# VESC_KS75600_ana_con.net
KiCad netlist of a schematic drawn in Altium Designer
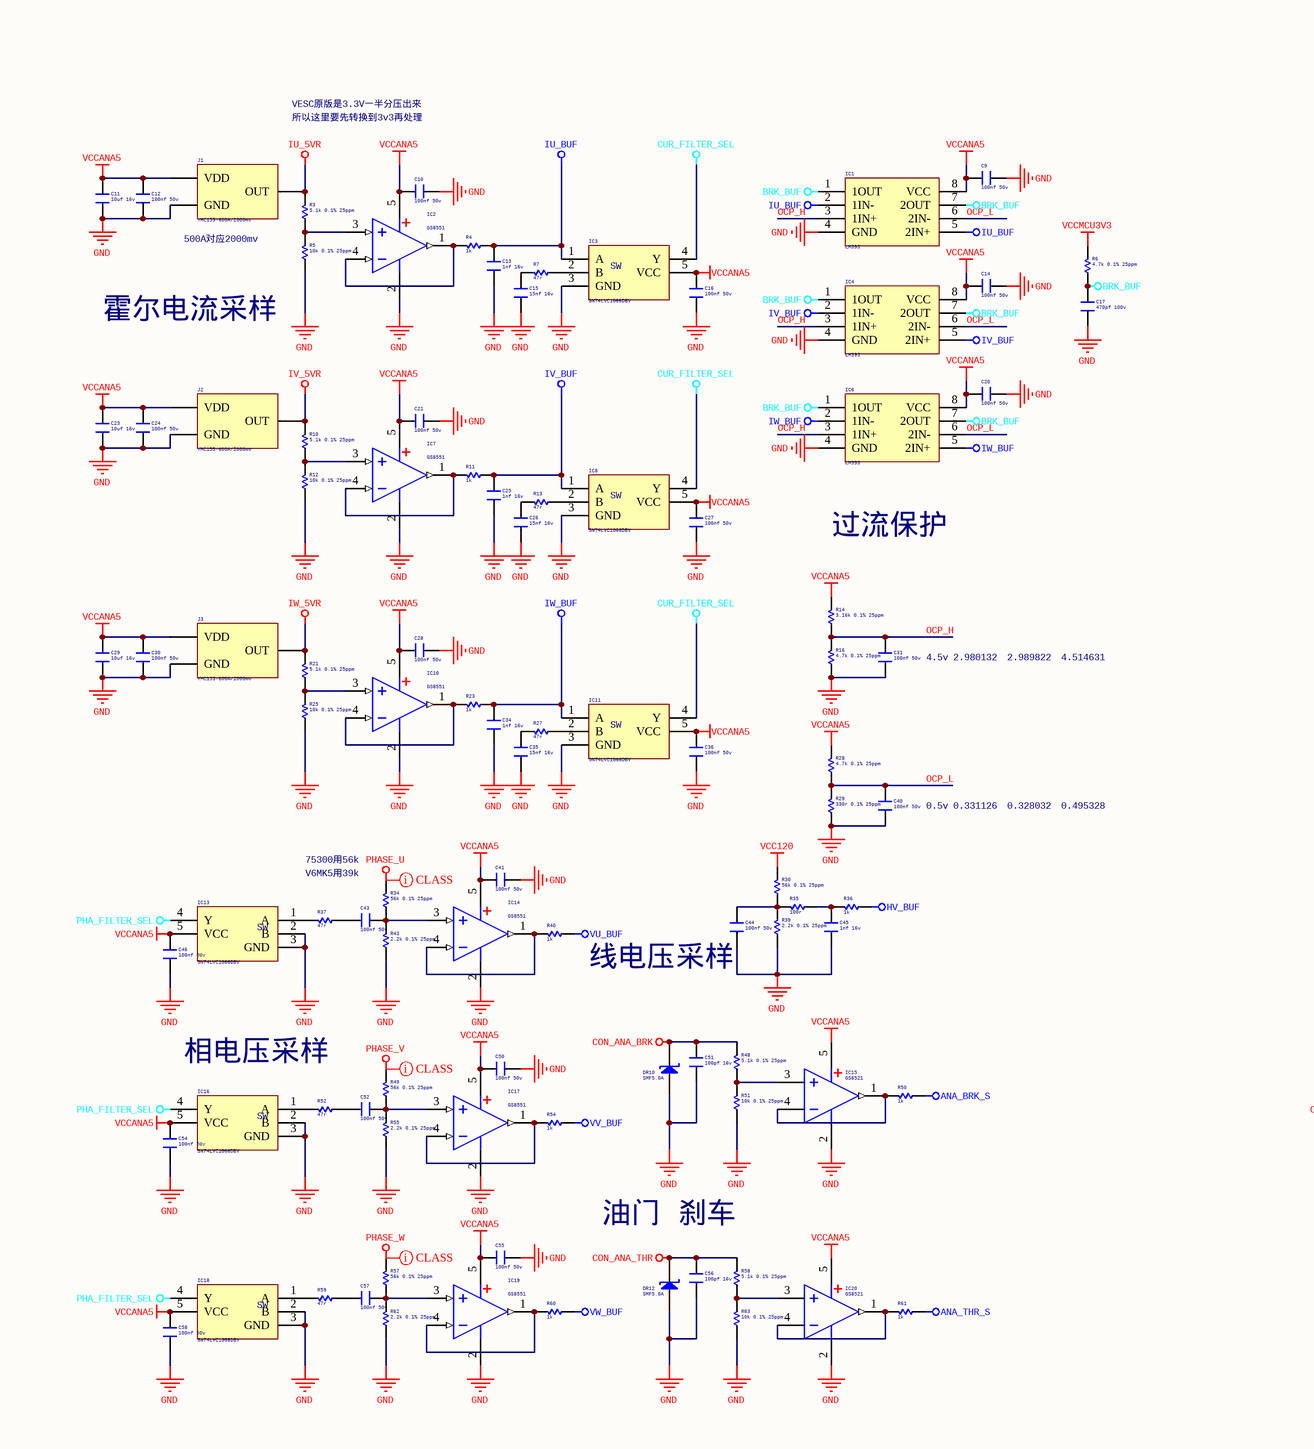
[diagram p0: VESC_KS75600_ana_con.SchDoc, left]
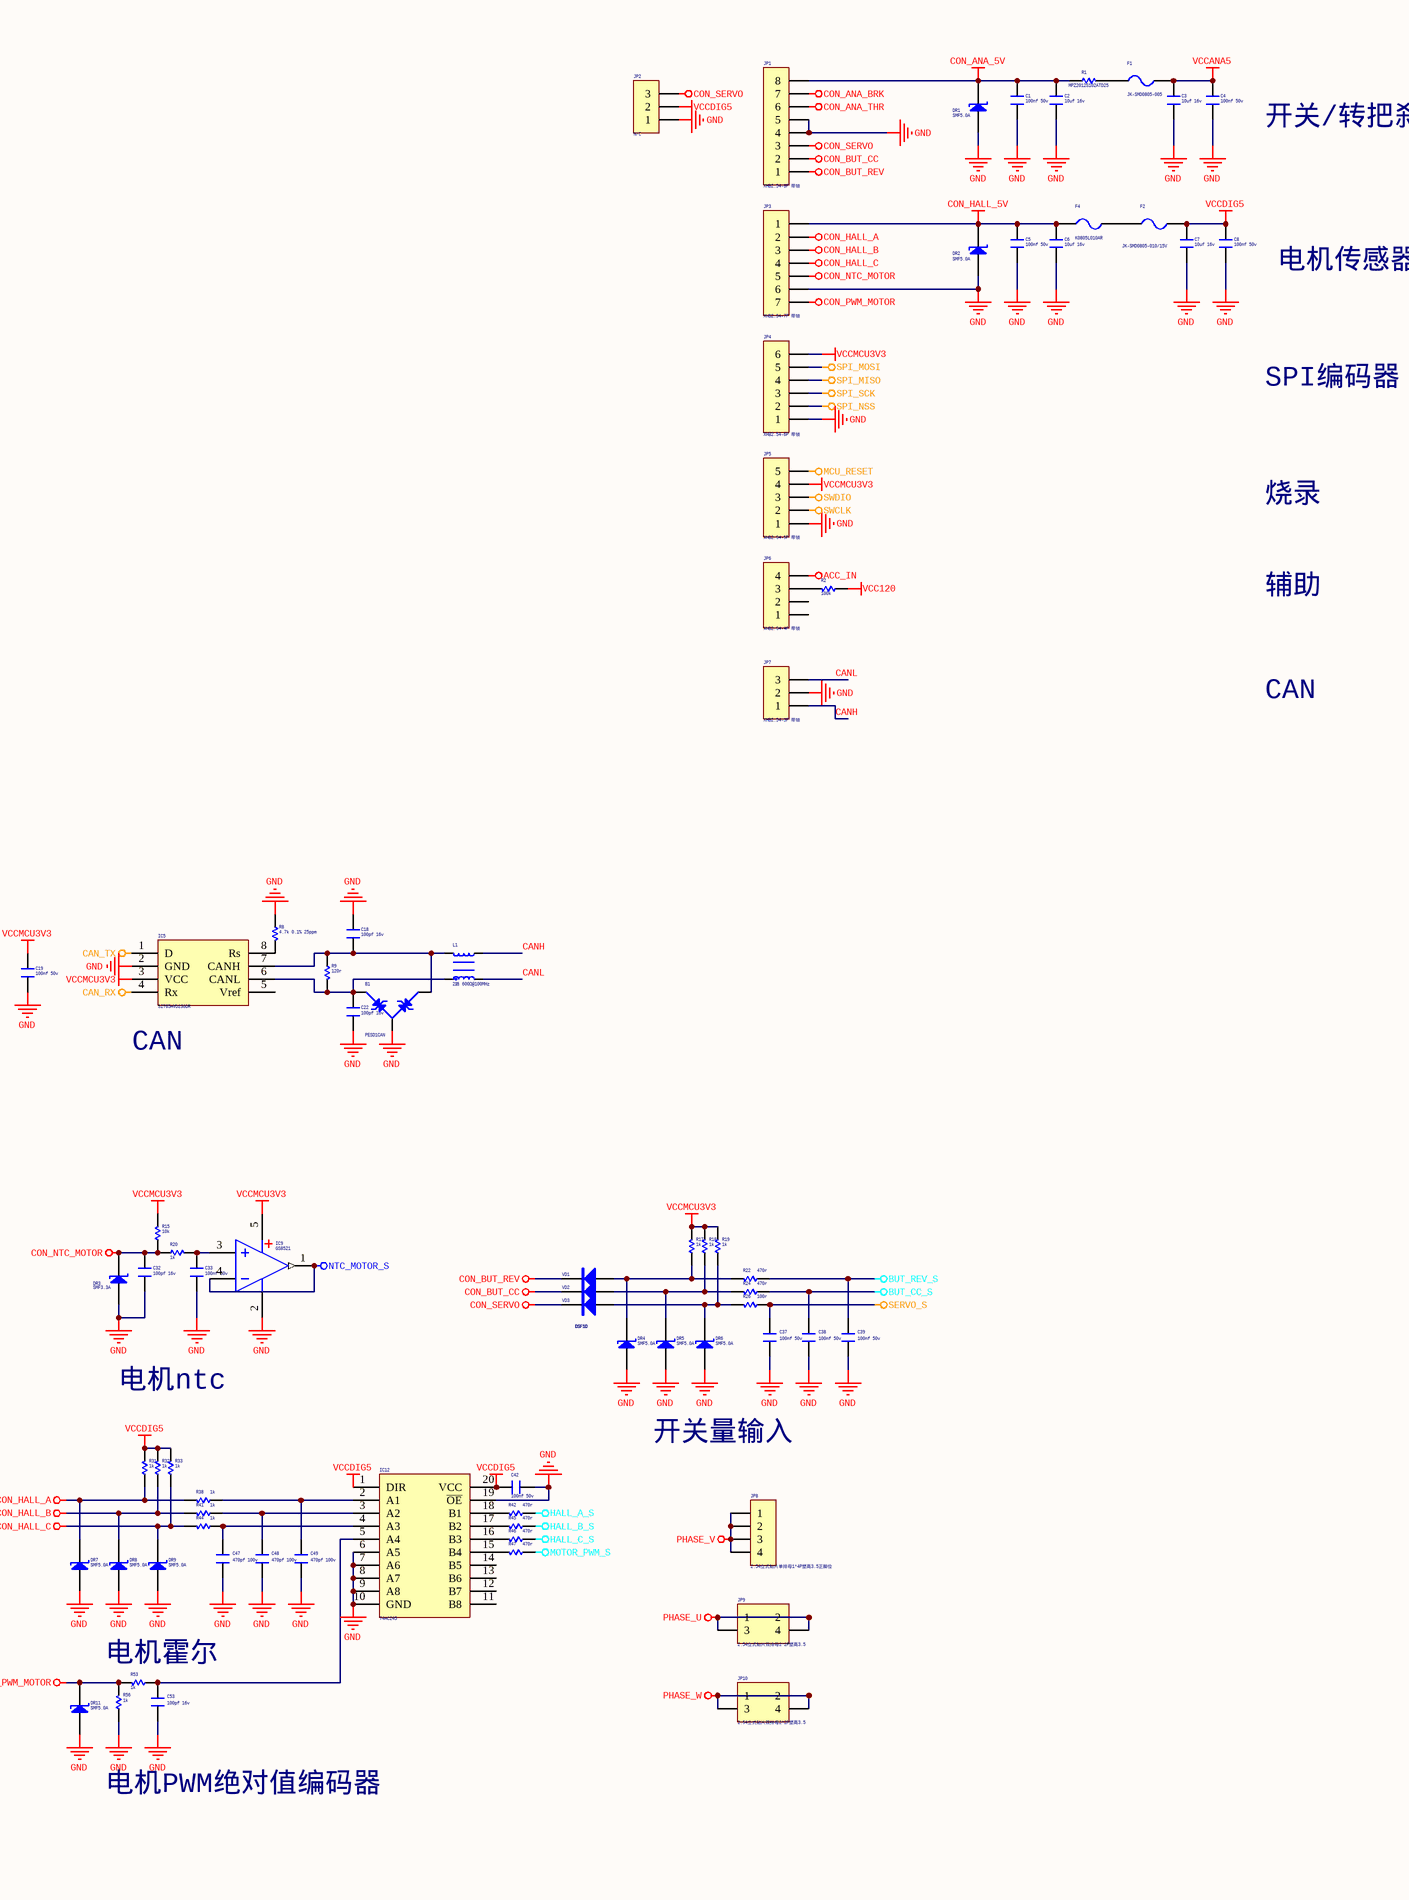
[diagram p1: VESC_KS75600_ana_con.SchDoc, right]

(export (version "E")
  (design (tool "Eeschema 10.0.6"))
  (components
    (comp (ref "B1")
      (value "PESD1CAN")
      (footprint "SOT23-3L")
      (description "7V+12V 双向双路TVS")
      (libsource (lib "二极管-整流桥") (part "SM712"))
    )
    (comp (ref "C1")
      (value "100nf 50v")
      (footprint "C 0603")
      (description "无极性贴片电容")
      (fields (field (name "VOLTAGE") "50v"))
      (libsource (lib "电阻-电容-电感") (part "C"))
    )
    (comp (ref "C2")
      (value "10uf 16v")
      (footprint "C 0805")
      (description "无极性贴片电容")
      (fields (field (name "VOLTAGE") "16v"))
      (libsource (lib "电阻-电容-电感") (part "C"))
    )
    (comp (ref "C3")
      (value "10uf 16v")
      (footprint "C 0805")
      (description "无极性贴片电容")
      (fields (field (name "VOLTAGE") "16v"))
      (libsource (lib "电阻-电容-电感") (part "C"))
    )
    (comp (ref "C4")
      (value "100nf 50v")
      (footprint "C 0603")
      (description "无极性贴片电容")
      (fields (field (name "VOLTAGE") "50v"))
      (libsource (lib "电阻-电容-电感") (part "C"))
    )
    (comp (ref "C5")
      (value "100nf 50v")
      (footprint "C 0603")
      (description "无极性贴片电容")
      (fields (field (name "VOLTAGE") "50v"))
      (libsource (lib "电阻-电容-电感") (part "C"))
    )
    (comp (ref "C6")
      (value "10uf 16v")
      (footprint "C 0805")
      (description "无极性贴片电容")
      (fields (field (name "VOLTAGE") "16v"))
      (libsource (lib "电阻-电容-电感") (part "C"))
    )
    (comp (ref "C7")
      (value "10uf 16v")
      (footprint "C 0805")
      (description "无极性贴片电容")
      (fields (field (name "VOLTAGE") "16v"))
      (libsource (lib "电阻-电容-电感") (part "C"))
    )
    (comp (ref "C8")
      (value "100nf 50v")
      (footprint "C 0603")
      (description "无极性贴片电容")
      (fields (field (name "VOLTAGE") "50v"))
      (libsource (lib "电阻-电容-电感") (part "C"))
    )
    (comp (ref "C9")
      (value "100nf 50v")
      (footprint "C 0603")
      (description "无极性贴片电容")
      (fields (field (name "VOLTAGE") "50v"))
      (libsource (lib "电阻-电容-电感") (part "C"))
    )
    (comp (ref "C10")
      (value "100nf 50v")
      (footprint "C 0603")
      (description "无极性贴片电容")
      (fields (field (name "VOLTAGE") "50v"))
      (libsource (lib "电阻-电容-电感") (part "C"))
    )
    (comp (ref "C11")
      (value "10uf 16v")
      (footprint "C 0805")
      (description "无极性贴片电容")
      (fields (field (name "VOLTAGE") "16v"))
      (libsource (lib "电阻-电容-电感") (part "C"))
    )
    (comp (ref "C12")
      (value "100nf 50v")
      (footprint "C 0603")
      (description "无极性贴片电容")
      (fields (field (name "VOLTAGE") "50v"))
      (libsource (lib "电阻-电容-电感") (part "C"))
    )
    (comp (ref "C13")
      (value "1nf 16v")
      (footprint "C 0603")
      (description "无极性贴片电容")
      (fields (field (name "VOLTAGE") "16v"))
      (libsource (lib "电阻-电容-电感") (part "C"))
    )
    (comp (ref "C14")
      (value "100nf 50v")
      (footprint "C 0603")
      (description "无极性贴片电容")
      (fields (field (name "VOLTAGE") "50v"))
      (libsource (lib "电阻-电容-电感") (part "C"))
    )
    (comp (ref "C15")
      (value "15nf 16v")
      (footprint "C 0603")
      (description "无极性贴片电容")
      (fields (field (name "VOLTAGE") "16v"))
      (libsource (lib "电阻-电容-电感") (part "C"))
    )
    (comp (ref "C16")
      (value "100nf 50v")
      (footprint "C 0603")
      (description "无极性贴片电容")
      (fields (field (name "VOLTAGE") "50v"))
      (libsource (lib "电阻-电容-电感") (part "C"))
    )
    (comp (ref "C17")
      (value "470pf 100v")
      (footprint "C 0805")
      (description "无极性贴片电容")
      (fields (field (name "VOLTAGE") "100v"))
      (libsource (lib "电阻-电容-电感") (part "C"))
    )
    (comp (ref "C18")
      (value "100pf 16v")
      (footprint "C 0603")
      (description "无极性贴片电容")
      (fields (field (name "VOLTAGE") "16v"))
      (libsource (lib "电阻-电容-电感") (part "C"))
    )
    (comp (ref "C19")
      (value "100nf 50v")
      (footprint "C 0603")
      (description "无极性贴片电容")
      (fields (field (name "VOLTAGE") "50v"))
      (libsource (lib "电阻-电容-电感") (part "C"))
    )
    (comp (ref "C20")
      (value "100nf 50v")
      (footprint "C 0603")
      (description "无极性贴片电容")
      (fields (field (name "VOLTAGE") "50v"))
      (libsource (lib "电阻-电容-电感") (part "C"))
    )
    (comp (ref "C21")
      (value "100nf 50v")
      (footprint "C 0603")
      (description "无极性贴片电容")
      (fields (field (name "VOLTAGE") "50v"))
      (libsource (lib "电阻-电容-电感") (part "C"))
    )
    (comp (ref "C22")
      (value "100pf 16v")
      (footprint "C 0603")
      (description "无极性贴片电容")
      (fields (field (name "VOLTAGE") "16v"))
      (libsource (lib "电阻-电容-电感") (part "C"))
    )
    (comp (ref "C23")
      (value "10uf 16v")
      (footprint "C 0805")
      (description "无极性贴片电容")
      (fields (field (name "VOLTAGE") "16v"))
      (libsource (lib "电阻-电容-电感") (part "C"))
    )
    (comp (ref "C24")
      (value "100nf 50v")
      (footprint "C 0603")
      (description "无极性贴片电容")
      (fields (field (name "VOLTAGE") "50v"))
      (libsource (lib "电阻-电容-电感") (part "C"))
    )
    (comp (ref "C25")
      (value "1nf 16v")
      (footprint "C 0603")
      (description "无极性贴片电容")
      (fields (field (name "VOLTAGE") "16v"))
      (libsource (lib "电阻-电容-电感") (part "C"))
    )
    (comp (ref "C26")
      (value "15nf 16v")
      (footprint "C 0603")
      (description "无极性贴片电容")
      (fields (field (name "VOLTAGE") "16v"))
      (libsource (lib "电阻-电容-电感") (part "C"))
    )
    (comp (ref "C27")
      (value "100nf 50v")
      (footprint "C 0603")
      (description "无极性贴片电容")
      (fields (field (name "VOLTAGE") "50v"))
      (libsource (lib "电阻-电容-电感") (part "C"))
    )
    (comp (ref "C28")
      (value "100nf 50v")
      (footprint "C 0603")
      (description "无极性贴片电容")
      (fields (field (name "VOLTAGE") "50v"))
      (libsource (lib "电阻-电容-电感") (part "C"))
    )
    (comp (ref "C29")
      (value "10uf 16v")
      (footprint "C 0805")
      (description "无极性贴片电容")
      (fields (field (name "VOLTAGE") "16v"))
      (libsource (lib "电阻-电容-电感") (part "C"))
    )
    (comp (ref "C30")
      (value "100nf 50v")
      (footprint "C 0603")
      (description "无极性贴片电容")
      (fields (field (name "VOLTAGE") "50v"))
      (libsource (lib "电阻-电容-电感") (part "C"))
    )
    (comp (ref "C31")
      (value "100nf 50v")
      (footprint "C 0603")
      (description "无极性贴片电容")
      (fields (field (name "VOLTAGE") "50v"))
      (libsource (lib "电阻-电容-电感") (part "C"))
    )
    (comp (ref "C32")
      (value "100pf 16v")
      (footprint "C 0603")
      (description "无极性贴片电容")
      (fields (field (name "VOLTAGE") "16v"))
      (libsource (lib "电阻-电容-电感") (part "C"))
    )
    (comp (ref "C33")
      (value "100nf 50v")
      (footprint "C 0603")
      (description "无极性贴片电容")
      (fields (field (name "VOLTAGE") "50v"))
      (libsource (lib "电阻-电容-电感") (part "C"))
    )
    (comp (ref "C34")
      (value "1nf 16v")
      (footprint "C 0603")
      (description "无极性贴片电容")
      (fields (field (name "VOLTAGE") "16v"))
      (libsource (lib "电阻-电容-电感") (part "C"))
    )
    (comp (ref "C35")
      (value "15nf 16v")
      (footprint "C 0603")
      (description "无极性贴片电容")
      (fields (field (name "VOLTAGE") "16v"))
      (libsource (lib "电阻-电容-电感") (part "C"))
    )
    (comp (ref "C36")
      (value "100nf 50v")
      (footprint "C 0603")
      (description "无极性贴片电容")
      (fields (field (name "VOLTAGE") "50v"))
      (libsource (lib "电阻-电容-电感") (part "C"))
    )
    (comp (ref "C37")
      (value "100nf 50v")
      (footprint "C 0805")
      (description "无极性贴片电容")
      (fields (field (name "VOLTAGE") "50v"))
      (libsource (lib "电阻-电容-电感") (part "C"))
    )
    (comp (ref "C38")
      (value "100nf 50v")
      (footprint "C 0805")
      (description "无极性贴片电容")
      (fields (field (name "VOLTAGE") "50v"))
      (libsource (lib "电阻-电容-电感") (part "C"))
    )
    (comp (ref "C39")
      (value "100nf 50v")
      (footprint "C 0805")
      (description "无极性贴片电容")
      (fields (field (name "VOLTAGE") "50v"))
      (libsource (lib "电阻-电容-电感") (part "C"))
    )
    (comp (ref "C40")
      (value "100nf 50v")
      (footprint "C 0603")
      (description "无极性贴片电容")
      (fields (field (name "VOLTAGE") "50v"))
      (libsource (lib "电阻-电容-电感") (part "C"))
    )
    (comp (ref "C41")
      (value "100nf 50v")
      (footprint "C 0603")
      (description "无极性贴片电容")
      (fields (field (name "VOLTAGE") "50v"))
      (libsource (lib "电阻-电容-电感") (part "C"))
    )
    (comp (ref "C42")
      (value "100nf 50v")
      (footprint "C 0603")
      (description "无极性贴片电容")
      (fields (field (name "VOLTAGE") "50v"))
      (libsource (lib "电阻-电容-电感") (part "C"))
    )
    (comp (ref "C43")
      (value "100nf 50v")
      (footprint "C 0805")
      (description "无极性贴片电容")
      (fields (field (name "VOLTAGE") "50v"))
      (libsource (lib "电阻-电容-电感") (part "C"))
    )
    (comp (ref "C44")
      (value "100nf 50v")
      (footprint "C 0805")
      (description "无极性贴片电容")
      (fields (field (name "VOLTAGE") "50v"))
      (libsource (lib "电阻-电容-电感") (part "C"))
    )
    (comp (ref "C45")
      (value "1nf 16v")
      (footprint "C 0603")
      (description "无极性贴片电容")
      (fields (field (name "VOLTAGE") "16v"))
      (libsource (lib "电阻-电容-电感") (part "C"))
    )
    (comp (ref "C46")
      (value "100nf 50v")
      (footprint "C 0603")
      (description "无极性贴片电容")
      (fields (field (name "VOLTAGE") "50v"))
      (libsource (lib "电阻-电容-电感") (part "C"))
    )
    (comp (ref "C47")
      (value "470pf 100v")
      (footprint "C 0805")
      (description "无极性贴片电容")
      (fields (field (name "VOLTAGE") "100v"))
      (libsource (lib "电阻-电容-电感") (part "C"))
    )
    (comp (ref "C48")
      (value "470pf 100v")
      (footprint "C 0805")
      (description "无极性贴片电容")
      (fields (field (name "VOLTAGE") "100v"))
      (libsource (lib "电阻-电容-电感") (part "C"))
    )
    (comp (ref "C49")
      (value "470pf 100v")
      (footprint "C 0805")
      (description "无极性贴片电容")
      (fields (field (name "VOLTAGE") "100v"))
      (libsource (lib "电阻-电容-电感") (part "C"))
    )
    (comp (ref "C50")
      (value "100nf 50v")
      (footprint "C 0603")
      (description "无极性贴片电容")
      (fields (field (name "VOLTAGE") "50v"))
      (libsource (lib "电阻-电容-电感") (part "C"))
    )
    (comp (ref "C51")
      (value "100pf 16v")
      (footprint "C 0603")
      (description "无极性贴片电容")
      (fields (field (name "VOLTAGE") "16v"))
      (libsource (lib "电阻-电容-电感") (part "C"))
    )
    (comp (ref "C52")
      (value "100nf 50v")
      (footprint "C 0805")
      (description "无极性贴片电容")
      (fields (field (name "VOLTAGE") "50v"))
      (libsource (lib "电阻-电容-电感") (part "C"))
    )
    (comp (ref "C53")
      (value "100pf 16v")
      (footprint "C 0805")
      (description "无极性贴片电容")
      (fields (field (name "VOLTAGE") "16v"))
      (libsource (lib "电阻-电容-电感") (part "C"))
    )
    (comp (ref "C54")
      (value "100nf 50v")
      (footprint "C 0603")
      (description "无极性贴片电容")
      (fields (field (name "VOLTAGE") "50v"))
      (libsource (lib "电阻-电容-电感") (part "C"))
    )
    (comp (ref "C55")
      (value "100nf 50v")
      (footprint "C 0603")
      (description "无极性贴片电容")
      (fields (field (name "VOLTAGE") "50v"))
      (libsource (lib "电阻-电容-电感") (part "C"))
    )
    (comp (ref "C56")
      (value "100pf 16v")
      (footprint "C 0603")
      (description "无极性贴片电容")
      (fields (field (name "VOLTAGE") "16v"))
      (libsource (lib "电阻-电容-电感") (part "C"))
    )
    (comp (ref "C57")
      (value "100nf 50v")
      (footprint "C 0805")
      (description "无极性贴片电容")
      (fields (field (name "VOLTAGE") "50v"))
      (libsource (lib "电阻-电容-电感") (part "C"))
    )
    (comp (ref "C58")
      (value "100nf 50v")
      (footprint "C 0603")
      (description "无极性贴片电容")
      (fields (field (name "VOLTAGE") "50v"))
      (libsource (lib "电阻-电容-电感") (part "C"))
    )
    (comp (ref "DR1")
      (value "SMF5.0A")
      (footprint "SOD-123F")
      (description "瞬态电压抑制二极管(单向)")
      (libsource (lib "二极管-整流桥") (part "DR_S"))
    )
    (comp (ref "DR2")
      (value "SMF5.0A")
      (footprint "SOD-123F")
      (description "瞬态电压抑制二极管(单向)")
      (libsource (lib "二极管-整流桥") (part "DR_S"))
    )
    (comp (ref "DR3")
      (value "SMF3.3A")
      (footprint "SOD-123F")
      (description "瞬态电压抑制二极管(单向)")
      (libsource (lib "二极管-整流桥") (part "DR_S"))
    )
    (comp (ref "DR4")
      (value "SMF5.0A")
      (footprint "SOD-123F")
      (description "瞬态电压抑制二极管(单向)")
      (libsource (lib "二极管-整流桥") (part "DR_S"))
    )
    (comp (ref "DR5")
      (value "SMF5.0A")
      (footprint "SOD-123F")
      (description "瞬态电压抑制二极管(单向)")
      (libsource (lib "二极管-整流桥") (part "DR_S"))
    )
    (comp (ref "DR6")
      (value "SMF5.0A")
      (footprint "SOD-123F")
      (description "瞬态电压抑制二极管(单向)")
      (libsource (lib "二极管-整流桥") (part "DR_S"))
    )
    (comp (ref "DR7")
      (value "SMF5.0A")
      (footprint "SOD-123F")
      (description "瞬态电压抑制二极管(单向)")
      (libsource (lib "二极管-整流桥") (part "DR_S"))
    )
    (comp (ref "DR8")
      (value "SMF5.0A")
      (footprint "SOD-123F")
      (description "瞬态电压抑制二极管(单向)")
      (libsource (lib "二极管-整流桥") (part "DR_S"))
    )
    (comp (ref "DR9")
      (value "SMF5.0A")
      (footprint "SOD-123F")
      (description "瞬态电压抑制二极管(单向)")
      (libsource (lib "二极管-整流桥") (part "DR_S"))
    )
    (comp (ref "DR10")
      (value "SMF5.0A")
      (footprint "SOD-123F")
      (description "瞬态电压抑制二极管(单向)")
      (libsource (lib "二极管-整流桥") (part "DR_S"))
    )
    (comp (ref "DR11")
      (value "SMF5.0A")
      (footprint "SOD-123F")
      (description "瞬态电压抑制二极管(单向)")
      (libsource (lib "二极管-整流桥") (part "DR_S"))
    )
    (comp (ref "DR12")
      (value "SMF5.0A")
      (footprint "SOD-123F")
      (description "瞬态电压抑制二极管(单向)")
      (libsource (lib "二极管-整流桥") (part "DR_S"))
    )
    (comp (ref "F1")
      (value "JK-SMD0805-005")
      (footprint "FU 0805")
      (description "贴片保险丝")
      (libsource (lib "保险丝-晶振") (part "FU"))
    )
    (comp (ref "F2")
      (value "JK-SMD0805-010/15V")
      (footprint "FU 0805")
      (description "贴片保险丝")
      (libsource (lib "保险丝-晶振") (part "FU"))
    )
    (comp (ref "F4")
      (value "K0805L010AR")
      (footprint "FU 0805")
      (description "贴片保险丝")
      (libsource (lib "保险丝-晶振") (part "FU"))
    )
    (comp (ref "IC1")
      (value "LM393")
      (footprint "SOP8_N")
      (description "双路电压比较")
      (libsource (lib "IC芯片") (part "LM393_A"))
    )
    (comp (ref "IC2")
      (value "GS8551")
      (footprint "SOT23-5L")
      (description "单运放 SOT23-5")
      (libsource (lib "IC芯片") (part "GS8331"))
    )
    (comp (ref "IC3")
      (value "SN74LVC1G66DBV")
      (footprint "SOT23-5N")
      (description "单路常开模拟开关 0.5ns 5.5Ω")
      (libsource (lib "") (part "SN74LVC1G66_1"))
    )
    (comp (ref "IC4")
      (value "LM393")
      (footprint "SOP8_N")
      (description "双路电压比较")
      (libsource (lib "IC芯片") (part "LM393_A"))
    )
    (comp (ref "IC5")
      (value "SIT65HVD230DR")
      (footprint "SOP8_N")
      (description "CAN芯片")
      (libsource (lib "IC芯片") (part "SN65HVD230"))
    )
    (comp (ref "IC6")
      (value "LM393")
      (footprint "SOP8_N")
      (description "双路电压比较")
      (libsource (lib "IC芯片") (part "LM393_A"))
    )
    (comp (ref "IC7")
      (value "GS8551")
      (footprint "SOT23-5L")
      (description "单运放 SOT23-5")
      (libsource (lib "IC芯片") (part "GS8331"))
    )
    (comp (ref "IC8")
      (value "SN74LVC1G66DBV")
      (footprint "SOT23-5N")
      (description "单路常开模拟开关 0.5ns 5.5Ω")
      (libsource (lib "") (part "SN74LVC1G66_1"))
    )
    (comp (ref "IC9")
      (value "GS8521")
      (footprint "SOT23-5N")
      (description "单运放 SOT23-5")
      (libsource (lib "") (part "GS8331_1"))
    )
    (comp (ref "IC10")
      (value "GS8551")
      (footprint "SOT23-5L")
      (description "单运放 SOT23-5")
      (libsource (lib "IC芯片") (part "GS8331"))
    )
    (comp (ref "IC11")
      (value "SN74LVC1G66DBV")
      (footprint "SOT23-5N")
      (description "单路常开模拟开关 0.5ns 5.5Ω")
      (libsource (lib "") (part "SN74LVC1G66_1"))
    )
    (comp (ref "IC12")
      (value "74HC245")
      (footprint "TSSOP20_N")
      (description "八线收发器")
      (libsource (lib "74系列芯片") (part "74HC245"))
    )
    (comp (ref "IC13")
      (value "SN74LVC1G66DBV")
      (footprint "SOT23-5N")
      (description "单路常开模拟开关 0.5ns 5.5Ω")
      (libsource (lib "74系列芯片") (part "SN74LVC1G66"))
    )
    (comp (ref "IC14")
      (value "GS8551")
      (footprint "SOT23-5L")
      (description "单运放 SOT23-5")
      (libsource (lib "IC芯片") (part "GS8331"))
    )
    (comp (ref "IC15")
      (value "GS8521")
      (footprint "SOT23-5N")
      (description "单运放 SOT23-5")
      (libsource (lib "") (part "GS8331_1"))
    )
    (comp (ref "IC16")
      (value "SN74LVC1G66DBV")
      (footprint "SOT23-5N")
      (description "单路常开模拟开关 0.5ns 5.5Ω")
      (libsource (lib "74系列芯片") (part "SN74LVC1G66"))
    )
    (comp (ref "IC17")
      (value "GS8551")
      (footprint "SOT23-5L")
      (description "单运放 SOT23-5")
      (libsource (lib "IC芯片") (part "GS8331"))
    )
    (comp (ref "IC18")
      (value "SN74LVC1G66DBV")
      (footprint "SOT23-5N")
      (description "单路常开模拟开关 0.5ns 5.5Ω")
      (libsource (lib "74系列芯片") (part "SN74LVC1G66"))
    )
    (comp (ref "IC19")
      (value "GS8551")
      (footprint "SOT23-5L")
      (description "单运放 SOT23-5")
      (libsource (lib "IC芯片") (part "GS8331"))
    )
    (comp (ref "IC20")
      (value "GS8521")
      (footprint "SOT23-5N")
      (description "单运放 SOT23-5")
      (libsource (lib "") (part "GS8331_1"))
    )
    (comp (ref "J1")
      (value "YMC15S-600A/2000mv")
      (footprint "YMC15S")
      (description "源弥科技 开环霍尔传感器")
      (libsource (lib "传感元件") (part "YMC15S"))
    )
    (comp (ref "J2")
      (value "YMC15S-600A/2000mv")
      (footprint "YMC15S")
      (description "源弥科技 开环霍尔传感器")
      (libsource (lib "传感元件") (part "YMC15S"))
    )
    (comp (ref "J3")
      (value "YMC15S-600A/2000mv")
      (footprint "YMC15S")
      (description "源弥科技 开环霍尔传感器")
      (libsource (lib "传感元件") (part "YMC15S"))
    )
    (comp (ref "JP1")
      (value "XHB2.54-8P 带锁")
      (footprint "XH2.54-8P")
      (description "8P接插件")
      (libsource (lib "接插件") (part "Header 8"))
    )
    (comp (ref "JP2")
      (value "N/C")
      (footprint "HDR-1X3")
      (description "3P接插件")
      (libsource (lib "接插件") (part "Header 3"))
    )
    (comp (ref "JP3")
      (value "XHB2.54-7P 带锁")
      (footprint "XH2.54-7P")
      (description "7P接插件")
      (libsource (lib "接插件") (part "Header 7"))
    )
    (comp (ref "JP4")
      (value "XHB2.54-6P 带锁")
      (footprint "XH2.54-6P")
      (description "6P接插件")
      (libsource (lib "接插件") (part "Header 6"))
    )
    (comp (ref "JP5")
      (value "XHB2.54-5P 带锁")
      (footprint "XH2.54-5P")
      (description "5P接插件")
      (libsource (lib "接插件") (part "Header 5"))
    )
    (comp (ref "JP6")
      (value "XHB2.54-4P 带锁")
      (footprint "XH2.54-4P")
      (description "4P接插件")
      (libsource (lib "接插件") (part "Header 4"))
    )
    (comp (ref "JP7")
      (value "XHB2.54-3P 带锁")
      (footprint "XH2.54-3P")
      (description "3P接插件")
      (libsource (lib "接插件") (part "Header 3"))
    )
    (comp (ref "JP8")
      (value "2.54立式贴片单排母1*4P塑高3.5正脚位")
      (footprint "2.54立贴错位排母 4P")
      (description "4P接插件")
      (libsource (lib "") (part "Header 4_1"))
    )
    (comp (ref "JP9")
      (value "2.54立式贴片双排母2*2P塑高3.5")
      (footprint "贴片2.54双排母 pcb开孔")
      (description "2*2P接插件")
      (libsource (lib "接插件") (part "Header 2X2"))
    )
    (comp (ref "JP10")
      (value "2.54立式贴片双排母2*2P塑高3.5")
      (footprint "贴片2.54双排母 pcb开孔")
      (description "2*2P接插件")
      (libsource (lib "接插件") (part "Header 2X2"))
    )
    (comp (ref "L1")
      (value "2路 600Ω@100MHz")
      (footprint "D_C_C_1206")
      (description "共模电感")
      (libsource (lib "电阻-电容-电感") (part "L-CMC"))
    )
    (comp (ref "R1")
      (value "MPZ2012S102ATD25")
      (footprint "R 0805")
      (description "贴片电阻")
      (libsource (lib "电阻-电容-电感") (part "R"))
    )
    (comp (ref "R2")
      (value "100k")
      (footprint "R 0805")
      (description "贴片电阻")
      (libsource (lib "电阻-电容-电感") (part "R"))
    )
    (comp (ref "R3")
      (value "5.1k 0.1% 25ppm")
      (footprint "R 0805-HP")
      (description "贴片电阻")
      (libsource (lib "电阻-电容-电感") (part "R"))
    )
    (comp (ref "R4")
      (value "1k")
      (footprint "R 0603")
      (description "贴片电阻")
      (libsource (lib "电阻-电容-电感") (part "R"))
    )
    (comp (ref "R5")
      (value "10k 0.1% 25ppm")
      (footprint "R 0805-HP")
      (description "贴片电阻")
      (libsource (lib "电阻-电容-电感") (part "R"))
    )
    (comp (ref "R6")
      (value "4.7k 0.1% 25ppm")
      (footprint "R 0805")
      (description "贴片电阻")
      (libsource (lib "电阻-电容-电感") (part "R"))
    )
    (comp (ref "R7")
      (value "47r")
      (footprint "R 0603")
      (description "贴片电阻")
      (libsource (lib "电阻-电容-电感") (part "R"))
    )
    (comp (ref "R8")
      (value "4.7k 0.1% 25ppm")
      (footprint "R 0805")
      (description "贴片电阻")
      (libsource (lib "电阻-电容-电感") (part "R"))
    )
    (comp (ref "R9")
      (value "120r")
      (footprint "R 0603")
      (description "贴片电阻")
      (libsource (lib "电阻-电容-电感") (part "R"))
    )
    (comp (ref "R10")
      (value "5.1k 0.1% 25ppm")
      (footprint "R 0805-HP")
      (description "贴片电阻")
      (libsource (lib "电阻-电容-电感") (part "R"))
    )
    (comp (ref "R11")
      (value "1k")
      (footprint "R 0603")
      (description "贴片电阻")
      (libsource (lib "电阻-电容-电感") (part "R"))
    )
    (comp (ref "R12")
      (value "10k 0.1% 25ppm")
      (footprint "R 0805-HP")
      (description "贴片电阻")
      (libsource (lib "电阻-电容-电感") (part "R"))
    )
    (comp (ref "R13")
      (value "47r")
      (footprint "R 0603")
      (description "贴片电阻")
      (libsource (lib "电阻-电容-电感") (part "R"))
    )
    (comp (ref "R14")
      (value "3.16k 0.1% 25ppm")
      (footprint "R 0805-HP")
      (description "贴片电阻")
      (libsource (lib "电阻-电容-电感") (part "R"))
    )
    (comp (ref "R15")
      (value "10k")
      (footprint "R 0603")
      (description "贴片电阻")
      (libsource (lib "电阻-电容-电感") (part "R"))
    )
    (comp (ref "R16")
      (value "4.7k 0.1% 25ppm")
      (footprint "R 0805")
      (description "贴片电阻")
      (libsource (lib "电阻-电容-电感") (part "R"))
    )
    (comp (ref "R17")
      (value "1k")
      (footprint "R 0603")
      (description "贴片电阻")
      (libsource (lib "电阻-电容-电感") (part "R"))
    )
    (comp (ref "R18")
      (value "1k")
      (footprint "R 0603")
      (description "贴片电阻")
      (libsource (lib "电阻-电容-电感") (part "R"))
    )
    (comp (ref "R19")
      (value "1k")
      (footprint "R 0603")
      (description "贴片电阻")
      (libsource (lib "电阻-电容-电感") (part "R"))
    )
    (comp (ref "R20")
      (value "1k")
      (footprint "R 0603")
      (description "贴片电阻")
      (libsource (lib "电阻-电容-电感") (part "R"))
    )
    (comp (ref "R21")
      (value "5.1k 0.1% 25ppm")
      (footprint "R 0805-HP")
      (description "贴片电阻")
      (libsource (lib "电阻-电容-电感") (part "R"))
    )
    (comp (ref "R22")
      (value "470r")
      (footprint "R 0603")
      (description "贴片电阻")
      (libsource (lib "电阻-电容-电感") (part "R"))
    )
    (comp (ref "R23")
      (value "1k")
      (footprint "R 0603")
      (description "贴片电阻")
      (libsource (lib "电阻-电容-电感") (part "R"))
    )
    (comp (ref "R24")
      (value "470r")
      (footprint "R 0603")
      (description "贴片电阻")
      (libsource (lib "电阻-电容-电感") (part "R"))
    )
    (comp (ref "R25")
      (value "10k 0.1% 25ppm")
      (footprint "R 0805-HP")
      (description "贴片电阻")
      (libsource (lib "电阻-电容-电感") (part "R"))
    )
    (comp (ref "R26")
      (value "100r")
      (footprint "R 0603")
      (description "贴片电阻")
      (libsource (lib "电阻-电容-电感") (part "R"))
    )
    (comp (ref "R27")
      (value "47r")
      (footprint "R 0603")
      (description "贴片电阻")
      (libsource (lib "电阻-电容-电感") (part "R"))
    )
    (comp (ref "R28")
      (value "4.7k 0.1% 25ppm")
      (footprint "R 0805")
      (description "贴片电阻")
      (libsource (lib "电阻-电容-电感") (part "R"))
    )
    (comp (ref "R29")
      (value "330r 0.1% 25ppm")
      (footprint "R 0805-HP")
      (description "贴片电阻")
      (libsource (lib "电阻-电容-电感") (part "R"))
    )
    (comp (ref "R30")
      (value "56k 0.1% 25ppm")
      (footprint "R 0805-HP")
      (description "贴片电阻")
      (libsource (lib "电阻-电容-电感") (part "R"))
    )
    (comp (ref "R31")
      (value "1k")
      (footprint "R 0603")
      (description "贴片电阻")
      (libsource (lib "电阻-电容-电感") (part "R"))
    )
    (comp (ref "R32")
      (value "1k")
      (footprint "R 0603")
      (description "贴片电阻")
      (libsource (lib "电阻-电容-电感") (part "R"))
    )
    (comp (ref "R33")
      (value "1k")
      (footprint "R 0603")
      (description "贴片电阻")
      (libsource (lib "电阻-电容-电感") (part "R"))
    )
    (comp (ref "R34")
      (value "56k 0.1% 25ppm")
      (footprint "R 0805-HP")
      (description "贴片电阻")
      (libsource (lib "电阻-电容-电感") (part "R"))
    )
    (comp (ref "R35")
      (value "100r")
      (footprint "R 0603")
      (description "贴片电阻")
      (libsource (lib "电阻-电容-电感") (part "R"))
    )
    (comp (ref "R36")
      (value "1k")
      (footprint "R 0603")
      (description "贴片电阻")
      (libsource (lib "电阻-电容-电感") (part "R"))
    )
    (comp (ref "R37")
      (value "47r")
      (footprint "R 0603")
      (description "贴片电阻")
      (libsource (lib "电阻-电容-电感") (part "R"))
    )
    (comp (ref "R38")
      (value "1k")
      (footprint "R 0603")
      (description "贴片电阻")
      (libsource (lib "电阻-电容-电感") (part "R"))
    )
    (comp (ref "R39")
      (value "2.2k 0.1% 25ppm")
      (footprint "R 0805-HP")
      (description "贴片电阻")
      (libsource (lib "电阻-电容-电感") (part "R"))
    )
    (comp (ref "R40")
      (value "1k")
      (footprint "R 0603")
      (description "贴片电阻")
      (libsource (lib "电阻-电容-电感") (part "R"))
    )
    (comp (ref "R41")
      (value "1k")
      (footprint "R 0603")
      (description "贴片电阻")
      (libsource (lib "电阻-电容-电感") (part "R"))
    )
    (comp (ref "R42")
      (value "470r")
      (footprint "R 0603")
      (description "贴片电阻")
      (libsource (lib "电阻-电容-电感") (part "R"))
    )
    (comp (ref "R43")
      (value "2.2k 0.1% 25ppm")
      (footprint "R 0805-HP")
      (description "贴片电阻")
      (libsource (lib "电阻-电容-电感") (part "R"))
    )
    (comp (ref "R44")
      (value "1k")
      (footprint "R 0603")
      (description "贴片电阻")
      (libsource (lib "电阻-电容-电感") (part "R"))
    )
    (comp (ref "R45")
      (value "470r")
      (footprint "R 0603")
      (description "贴片电阻")
      (libsource (lib "电阻-电容-电感") (part "R"))
    )
    (comp (ref "R46")
      (value "470r")
      (footprint "R 0603")
      (description "贴片电阻")
      (libsource (lib "电阻-电容-电感") (part "R"))
    )
    (comp (ref "R47")
      (value "470r")
      (footprint "R 0603")
      (description "贴片电阻")
      (libsource (lib "电阻-电容-电感") (part "R"))
    )
    (comp (ref "R48")
      (value "5.1k 0.1% 25ppm")
      (footprint "R 0805-HP")
      (description "贴片电阻")
      (libsource (lib "电阻-电容-电感") (part "R"))
    )
    (comp (ref "R49")
      (value "56k 0.1% 25ppm")
      (footprint "R 0805-HP")
      (description "贴片电阻")
      (libsource (lib "电阻-电容-电感") (part "R"))
    )
    (comp (ref "R50")
      (value "1k")
      (footprint "R 0603")
      (description "贴片电阻")
      (libsource (lib "电阻-电容-电感") (part "R"))
    )
    (comp (ref "R51")
      (value "10k 0.1% 25ppm")
      (footprint "R 0805-HP")
      (description "贴片电阻")
      (libsource (lib "电阻-电容-电感") (part "R"))
    )
    (comp (ref "R52")
      (value "47r")
      (footprint "R 0603")
      (description "贴片电阻")
      (libsource (lib "电阻-电容-电感") (part "R"))
    )
    (comp (ref "R53")
      (value "1k")
      (footprint "R 0603")
      (description "贴片电阻")
      (libsource (lib "电阻-电容-电感") (part "R"))
    )
    (comp (ref "R54")
      (value "1k")
      (footprint "R 0603")
      (description "贴片电阻")
      (libsource (lib "电阻-电容-电感") (part "R"))
    )
    (comp (ref "R55")
      (value "2.2k 0.1% 25ppm")
      (footprint "R 0805-HP")
      (description "贴片电阻")
      (libsource (lib "电阻-电容-电感") (part "R"))
    )
    (comp (ref "R56")
      (value "1k")
      (footprint "R 0603")
      (description "贴片电阻")
      (libsource (lib "电阻-电容-电感") (part "R"))
    )
    (comp (ref "R57")
      (value "56k 0.1% 25ppm")
      (footprint "R 0805-HP")
      (description "贴片电阻")
      (libsource (lib "电阻-电容-电感") (part "R"))
    )
    (comp (ref "R58")
      (value "5.1k 0.1% 25ppm")
      (footprint "R 0805-HP")
      (description "贴片电阻")
      (libsource (lib "电阻-电容-电感") (part "R"))
    )
    (comp (ref "R59")
      (value "47r")
      (footprint "R 0603")
      (description "贴片电阻")
      (libsource (lib "电阻-电容-电感") (part "R"))
    )
    (comp (ref "R60")
      (value "1k")
      (footprint "R 0603")
      (description "贴片电阻")
      (libsource (lib "电阻-电容-电感") (part "R"))
    )
    (comp (ref "R61")
      (value "1k")
      (footprint "R 0603")
      (description "贴片电阻")
      (libsource (lib "电阻-电容-电感") (part "R"))
    )
    (comp (ref "R62")
      (value "2.2k 0.1% 25ppm")
      (footprint "R 0805-HP")
      (description "贴片电阻")
      (libsource (lib "电阻-电容-电感") (part "R"))
    )
    (comp (ref "R63")
      (value "10k 0.1% 25ppm")
      (footprint "R 0805-HP")
      (description "贴片电阻")
      (libsource (lib "电阻-电容-电感") (part "R"))
    )
    (comp (ref "VD1")
      (value "DSF1D")
      (footprint "SOD-123")
      (description "肖特基二极管")
      (libsource (lib "二极管-整流桥") (part "SR540"))
    )
    (comp (ref "VD2")
      (value "DSF1D")
      (footprint "SOD-123")
      (description "肖特基二极管")
      (libsource (lib "二极管-整流桥") (part "SR540"))
    )
    (comp (ref "VD3")
      (value "DSF1D")
      (footprint "SOD-123")
      (description "肖特基二极管")
      (libsource (lib "二极管-整流桥") (part "SR540"))
    )
  )
  (nets
    (net (code "1") (name "/CANH") (class "Default")
      (node (ref "JP7") (pin "1") (pinfunction "1_1") (pintype "passive"))
      (node (ref "L1") (pin "3") (pinfunction "3_3") (pintype "passive"))
    )
    (net (code "2") (name "/CANL") (class "Default")
      (node (ref "JP7") (pin "3") (pinfunction "3_3") (pintype "passive"))
      (node (ref "L1") (pin "2") (pinfunction "2_2") (pintype "passive"))
    )
    (net (code "3") (name "/OCP_H") (class "Default")
      (node (ref "C31") (pin "2") (pinfunction "2_2") (pintype "passive"))
      (node (ref "IC1") (pin "3") (pinfunction "1IN+_3") (pintype "passive"))
      (node (ref "IC4") (pin "3") (pinfunction "1IN+_3") (pintype "passive"))
      (node (ref "IC6") (pin "3") (pinfunction "1IN+_3") (pintype "passive"))
      (node (ref "R14") (pin "1") (pinfunction "1_1") (pintype "passive"))
      (node (ref "R16") (pin "2") (pinfunction "2_2") (pintype "passive"))
    )
    (net (code "4") (name "/OCP_L") (class "Default")
      (node (ref "C40") (pin "2") (pinfunction "2_2") (pintype "passive"))
      (node (ref "IC1") (pin "6") (pinfunction "2IN-_6") (pintype "passive"))
      (node (ref "IC4") (pin "6") (pinfunction "2IN-_6") (pintype "passive"))
      (node (ref "IC6") (pin "6") (pinfunction "2IN-_6") (pintype "passive"))
      (node (ref "R28") (pin "1") (pinfunction "1_1") (pintype "passive"))
      (node (ref "R29") (pin "2") (pinfunction "2_2") (pintype "passive"))
    )
    (net (code "5") (name "ACC_IN") (class "Default")
      (node (ref "JP6") (pin "4") (pinfunction "4_4") (pintype "passive"))
    )
    (net (code "6") (name "ANA_BRK_S") (class "Default")
      (node (ref "R50") (pin "1") (pinfunction "1_1") (pintype "passive"))
    )
    (net (code "7") (name "ANA_THR_S") (class "Default")
      (node (ref "R61") (pin "1") (pinfunction "1_1") (pintype "passive"))
    )
    (net (code "8") (name "BRK_BUF") (class "Default")
      (node (ref "C17") (pin "1") (pinfunction "1_1") (pintype "passive"))
      (node (ref "IC1") (pin "1") (pinfunction "1OUT_1") (pintype "passive"))
      (node (ref "IC1") (pin "7") (pinfunction "2OUT_7") (pintype "passive"))
      (node (ref "IC4") (pin "1") (pinfunction "1OUT_1") (pintype "passive"))
      (node (ref "IC4") (pin "7") (pinfunction "2OUT_7") (pintype "passive"))
      (node (ref "IC6") (pin "1") (pinfunction "1OUT_1") (pintype "passive"))
      (node (ref "IC6") (pin "7") (pinfunction "2OUT_7") (pintype "passive"))
      (node (ref "R6") (pin "1") (pinfunction "1_1") (pintype "passive"))
    )
    (net (code "9") (name "BUT_CC_S") (class "Default")
      (node (ref "C38") (pin "2") (pinfunction "2_2") (pintype "passive"))
      (node (ref "R24") (pin "1") (pinfunction "1_1") (pintype "passive"))
    )
    (net (code "10") (name "BUT_REV_S") (class "Default")
      (node (ref "C39") (pin "2") (pinfunction "2_2") (pintype "passive"))
      (node (ref "R22") (pin "1") (pinfunction "1_1") (pintype "passive"))
    )
    (net (code "11") (name "CAN_RX") (class "Default")
      (node (ref "IC5") (pin "4") (pinfunction "Rx_4") (pintype "passive"))
    )
    (net (code "12") (name "CAN_TX") (class "Default")
      (node (ref "IC5") (pin "1") (pinfunction "D_1") (pintype "passive"))
    )
    (net (code "13") (name "CON_ANA_5V") (class "Default")
      (node (ref "C1") (pin "1") (pinfunction "1_1") (pintype "passive"))
      (node (ref "C2") (pin "1") (pinfunction "1_1") (pintype "passive"))
      (node (ref "DR1") (pin "2") (pinfunction "K_2") (pintype "passive"))
      (node (ref "JP1") (pin "8") (pinfunction "8_8") (pintype "passive"))
      (node (ref "R1") (pin "1") (pinfunction "1_1") (pintype "passive"))
    )
    (net (code "14") (name "CON_ANA_BRK") (class "Default")
      (node (ref "C51") (pin "2") (pinfunction "2_2") (pintype "passive"))
      (node (ref "DR10") (pin "2") (pinfunction "K_2") (pintype "passive"))
      (node (ref "JP1") (pin "7") (pinfunction "7_7") (pintype "passive"))
      (node (ref "R48") (pin "2") (pinfunction "2_2") (pintype "passive"))
    )
    (net (code "15") (name "CON_ANA_THR") (class "Default")
      (node (ref "C56") (pin "2") (pinfunction "2_2") (pintype "passive"))
      (node (ref "DR12") (pin "2") (pinfunction "K_2") (pintype "passive"))
      (node (ref "JP1") (pin "6") (pinfunction "6_6") (pintype "passive"))
      (node (ref "R58") (pin "2") (pinfunction "2_2") (pintype "passive"))
    )
    (net (code "16") (name "CON_BUT_CC") (class "Default")
      (node (ref "JP1") (pin "2") (pinfunction "2_2") (pintype "passive"))
      (node (ref "VD2") (pin "2") (pinfunction "K_2") (pintype "passive"))
    )
    (net (code "17") (name "CON_BUT_REV") (class "Default")
      (node (ref "JP1") (pin "1") (pinfunction "1_1") (pintype "passive"))
      (node (ref "VD1") (pin "2") (pinfunction "K_2") (pintype "passive"))
    )
    (net (code "18") (name "CON_HALL_5V") (class "Default")
      (node (ref "C5") (pin "1") (pinfunction "1_1") (pintype "passive"))
      (node (ref "C6") (pin "1") (pinfunction "1_1") (pintype "passive"))
      (node (ref "DR2") (pin "2") (pinfunction "K_2") (pintype "passive"))
      (node (ref "F4") (pin "2") (pinfunction "2_2") (pintype "passive"))
      (node (ref "JP3") (pin "1") (pinfunction "1_1") (pintype "passive"))
    )
    (net (code "19") (name "CON_HALL_A") (class "Default")
      (node (ref "DR7") (pin "2") (pinfunction "K_2") (pintype "passive"))
      (node (ref "JP3") (pin "2") (pinfunction "2_2") (pintype "passive"))
      (node (ref "R31") (pin "1") (pinfunction "1_1") (pintype "passive"))
      (node (ref "R38") (pin "2") (pinfunction "2_2") (pintype "passive"))
    )
    (net (code "20") (name "CON_HALL_B") (class "Default")
      (node (ref "DR8") (pin "2") (pinfunction "K_2") (pintype "passive"))
      (node (ref "JP3") (pin "3") (pinfunction "3_3") (pintype "passive"))
      (node (ref "R32") (pin "1") (pinfunction "1_1") (pintype "passive"))
      (node (ref "R41") (pin "2") (pinfunction "2_2") (pintype "passive"))
    )
    (net (code "21") (name "CON_HALL_C") (class "Default")
      (node (ref "DR9") (pin "2") (pinfunction "K_2") (pintype "passive"))
      (node (ref "JP3") (pin "4") (pinfunction "4_4") (pintype "passive"))
      (node (ref "R33") (pin "1") (pinfunction "1_1") (pintype "passive"))
      (node (ref "R44") (pin "2") (pinfunction "2_2") (pintype "passive"))
    )
    (net (code "22") (name "CON_NTC_MOTOR") (class "Default")
      (node (ref "C32") (pin "2") (pinfunction "2_2") (pintype "passive"))
      (node (ref "DR3") (pin "2") (pinfunction "K_2") (pintype "passive"))
      (node (ref "JP3") (pin "5") (pinfunction "5_5") (pintype "passive"))
      (node (ref "R15") (pin "1") (pinfunction "1_1") (pintype "passive"))
      (node (ref "R20") (pin "1") (pinfunction "1_1") (pintype "passive"))
    )
    (net (code "23") (name "CON_PWM_MOTOR") (class "Default")
      (node (ref "DR11") (pin "2") (pinfunction "K_2") (pintype "passive"))
      (node (ref "JP3") (pin "7") (pinfunction "7_7") (pintype "passive"))
      (node (ref "R53") (pin "2") (pinfunction "2_2") (pintype "passive"))
      (node (ref "R56") (pin "2") (pinfunction "2_2") (pintype "passive"))
    )
    (net (code "24") (name "CON_SERVO") (class "Default")
      (node (ref "JP1") (pin "3") (pinfunction "3_3") (pintype "passive"))
      (node (ref "JP2") (pin "3") (pinfunction "3_3") (pintype "passive"))
      (node (ref "VD3") (pin "2") (pinfunction "K_2") (pintype "passive"))
    )
    (net (code "25") (name "CUR_FILTER_SEL") (class "Default")
      (node (ref "IC11") (pin "4") (pinfunction "Y_4") (pintype "passive"))
      (node (ref "IC3") (pin "4") (pinfunction "Y_4") (pintype "passive"))
      (node (ref "IC8") (pin "4") (pinfunction "Y_4") (pintype "passive"))
    )
    (net (code "26") (name "GND") (class "Default")
      (node (ref "B1") (pin "3") (pinfunction "3_3") (pintype "passive"))
      (node (ref "C1") (pin "2") (pinfunction "2_2") (pintype "passive"))
      (node (ref "C10") (pin "2") (pinfunction "2_2") (pintype "passive"))
      (node (ref "C11") (pin "1") (pinfunction "1_1") (pintype "passive"))
      (node (ref "C12") (pin "2") (pinfunction "2_2") (pintype "passive"))
      (node (ref "C13") (pin "2") (pinfunction "2_2") (pintype "passive"))
      (node (ref "C14") (pin "2") (pinfunction "2_2") (pintype "passive"))
      (node (ref "C15") (pin "2") (pinfunction "2_2") (pintype "passive"))
      (node (ref "C16") (pin "2") (pinfunction "2_2") (pintype "passive"))
      (node (ref "C17") (pin "2") (pinfunction "2_2") (pintype "passive"))
      (node (ref "C18") (pin "2") (pinfunction "2_2") (pintype "passive"))
      (node (ref "C19") (pin "2") (pinfunction "2_2") (pintype "passive"))
      (node (ref "C2") (pin "2") (pinfunction "2_2") (pintype "passive"))
      (node (ref "C20") (pin "2") (pinfunction "2_2") (pintype "passive"))
      (node (ref "C21") (pin "2") (pinfunction "2_2") (pintype "passive"))
      (node (ref "C22") (pin "1") (pinfunction "1_1") (pintype "passive"))
      (node (ref "C23") (pin "1") (pinfunction "1_1") (pintype "passive"))
      (node (ref "C24") (pin "2") (pinfunction "2_2") (pintype "passive"))
      (node (ref "C25") (pin "2") (pinfunction "2_2") (pintype "passive"))
      (node (ref "C26") (pin "2") (pinfunction "2_2") (pintype "passive"))
      (node (ref "C27") (pin "2") (pinfunction "2_2") (pintype "passive"))
      (node (ref "C28") (pin "2") (pinfunction "2_2") (pintype "passive"))
      (node (ref "C29") (pin "1") (pinfunction "1_1") (pintype "passive"))
      (node (ref "C3") (pin "2") (pinfunction "2_2") (pintype "passive"))
      (node (ref "C30") (pin "2") (pinfunction "2_2") (pintype "passive"))
      (node (ref "C31") (pin "1") (pinfunction "1_1") (pintype "passive"))
      (node (ref "C32") (pin "1") (pinfunction "1_1") (pintype "passive"))
      (node (ref "C33") (pin "1") (pinfunction "1_1") (pintype "passive"))
      (node (ref "C34") (pin "2") (pinfunction "2_2") (pintype "passive"))
      (node (ref "C35") (pin "2") (pinfunction "2_2") (pintype "passive"))
      (node (ref "C36") (pin "2") (pinfunction "2_2") (pintype "passive"))
      (node (ref "C37") (pin "1") (pinfunction "1_1") (pintype "passive"))
      (node (ref "C38") (pin "1") (pinfunction "1_1") (pintype "passive"))
      (node (ref "C39") (pin "1") (pinfunction "1_1") (pintype "passive"))
      (node (ref "C4") (pin "2") (pinfunction "2_2") (pintype "passive"))
      (node (ref "C40") (pin "1") (pinfunction "1_1") (pintype "passive"))
      (node (ref "C41") (pin "2") (pinfunction "2_2") (pintype "passive"))
      (node (ref "C42") (pin "2") (pinfunction "2_2") (pintype "passive"))
      (node (ref "C44") (pin "2") (pinfunction "2_2") (pintype "passive"))
      (node (ref "C45") (pin "2") (pinfunction "2_2") (pintype "passive"))
      (node (ref "C46") (pin "2") (pinfunction "2_2") (pintype "passive"))
      (node (ref "C47") (pin "1") (pinfunction "1_1") (pintype "passive"))
      (node (ref "C48") (pin "1") (pinfunction "1_1") (pintype "passive"))
      (node (ref "C49") (pin "1") (pinfunction "1_1") (pintype "passive"))
      (node (ref "C5") (pin "2") (pinfunction "2_2") (pintype "passive"))
      (node (ref "C50") (pin "2") (pinfunction "2_2") (pintype "passive"))
      (node (ref "C51") (pin "1") (pinfunction "1_1") (pintype "passive"))
      (node (ref "C53") (pin "1") (pinfunction "1_1") (pintype "passive"))
      (node (ref "C54") (pin "2") (pinfunction "2_2") (pintype "passive"))
      (node (ref "C55") (pin "2") (pinfunction "2_2") (pintype "passive"))
      (node (ref "C56") (pin "1") (pinfunction "1_1") (pintype "passive"))
      (node (ref "C58") (pin "2") (pinfunction "2_2") (pintype "passive"))
      (node (ref "C6") (pin "2") (pinfunction "2_2") (pintype "passive"))
      (node (ref "C7") (pin "2") (pinfunction "2_2") (pintype "passive"))
      (node (ref "C8") (pin "2") (pinfunction "2_2") (pintype "passive"))
      (node (ref "C9") (pin "2") (pinfunction "2_2") (pintype "passive"))
      (node (ref "DR1") (pin "1") (pinfunction "A_1") (pintype "passive"))
      (node (ref "DR10") (pin "1") (pinfunction "A_1") (pintype "passive"))
      (node (ref "DR11") (pin "1") (pinfunction "A_1") (pintype "passive"))
      (node (ref "DR12") (pin "1") (pinfunction "A_1") (pintype "passive"))
      (node (ref "DR2") (pin "1") (pinfunction "A_1") (pintype "passive"))
      (node (ref "DR3") (pin "1") (pinfunction "A_1") (pintype "passive"))
      (node (ref "DR4") (pin "1") (pinfunction "A_1") (pintype "passive"))
      (node (ref "DR5") (pin "1") (pinfunction "A_1") (pintype "passive"))
      (node (ref "DR6") (pin "1") (pinfunction "A_1") (pintype "passive"))
      (node (ref "DR7") (pin "1") (pinfunction "A_1") (pintype "passive"))
      (node (ref "DR8") (pin "1") (pinfunction "A_1") (pintype "passive"))
      (node (ref "DR9") (pin "1") (pinfunction "A_1") (pintype "passive"))
      (node (ref "IC1") (pin "4") (pinfunction "GND_4") (pintype "passive"))
      (node (ref "IC10") (pin "2") (pinfunction "V-_2") (pintype "power_in"))
      (node (ref "IC11") (pin "3") (pinfunction "GND_3") (pintype "passive"))
      (node (ref "IC12") (pin "10") (pinfunction "GND_10") (pintype "passive"))
      (node (ref "IC12") (pin "19") (pinfunction "~{OE}_19") (pintype "passive"))
      (node (ref "IC12") (pin "6") (pinfunction "A5_6") (pintype "passive"))
      (node (ref "IC12") (pin "7") (pinfunction "A6_7") (pintype "passive"))
      (node (ref "IC12") (pin "8") (pinfunction "A7_8") (pintype "passive"))
      (node (ref "IC12") (pin "9") (pinfunction "A8_9") (pintype "passive"))
      (node (ref "IC13") (pin "2") (pinfunction "B_2") (pintype "passive"))
      (node (ref "IC13") (pin "3") (pinfunction "GND_3") (pintype "passive"))
      (node (ref "IC14") (pin "2") (pinfunction "V-_2") (pintype "power_in"))
      (node (ref "IC15") (pin "2") (pinfunction "V-_2") (pintype "passive"))
      (node (ref "IC16") (pin "2") (pinfunction "B_2") (pintype "passive"))
      (node (ref "IC16") (pin "3") (pinfunction "GND_3") (pintype "passive"))
      (node (ref "IC17") (pin "2") (pinfunction "V-_2") (pintype "power_in"))
      (node (ref "IC18") (pin "2") (pinfunction "B_2") (pintype "passive"))
      (node (ref "IC18") (pin "3") (pinfunction "GND_3") (pintype "passive"))
      (node (ref "IC19") (pin "2") (pinfunction "V-_2") (pintype "power_in"))
      (node (ref "IC2") (pin "2") (pinfunction "V-_2") (pintype "power_in"))
      (node (ref "IC20") (pin "2") (pinfunction "V-_2") (pintype "passive"))
      (node (ref "IC3") (pin "3") (pinfunction "GND_3") (pintype "passive"))
      (node (ref "IC4") (pin "4") (pinfunction "GND_4") (pintype "passive"))
      (node (ref "IC5") (pin "2") (pinfunction "GND_2") (pintype "passive"))
      (node (ref "IC6") (pin "4") (pinfunction "GND_4") (pintype "passive"))
      (node (ref "IC7") (pin "2") (pinfunction "V-_2") (pintype "power_in"))
      (node (ref "IC8") (pin "3") (pinfunction "GND_3") (pintype "passive"))
      (node (ref "IC9") (pin "2") (pinfunction "V-_2") (pintype "passive"))
      (node (ref "J1") (pin "2") (pinfunction "GND_2") (pintype "passive"))
      (node (ref "J2") (pin "2") (pinfunction "GND_2") (pintype "passive"))
      (node (ref "J3") (pin "2") (pinfunction "GND_2") (pintype "passive"))
      (node (ref "JP1") (pin "4") (pinfunction "4_4") (pintype "passive"))
      (node (ref "JP1") (pin "5") (pinfunction "5_5") (pintype "passive"))
      (node (ref "JP2") (pin "1") (pinfunction "1_1") (pintype "passive"))
      (node (ref "JP3") (pin "6") (pinfunction "6_6") (pintype "passive"))
      (node (ref "JP4") (pin "1") (pinfunction "1_1") (pintype "passive"))
      (node (ref "JP5") (pin "1") (pinfunction "1_1") (pintype "passive"))
      (node (ref "JP7") (pin "2") (pinfunction "2_2") (pintype "passive"))
      (node (ref "R12") (pin "1") (pinfunction "1_1") (pintype "passive"))
      (node (ref "R16") (pin "1") (pinfunction "1_1") (pintype "passive"))
      (node (ref "R25") (pin "1") (pinfunction "1_1") (pintype "passive"))
      (node (ref "R29") (pin "1") (pinfunction "1_1") (pintype "passive"))
      (node (ref "R39") (pin "1") (pinfunction "1_1") (pintype "passive"))
      (node (ref "R43") (pin "1") (pinfunction "1_1") (pintype "passive"))
      (node (ref "R5") (pin "1") (pinfunction "1_1") (pintype "passive"))
      (node (ref "R51") (pin "1") (pinfunction "1_1") (pintype "passive"))
      (node (ref "R55") (pin "1") (pinfunction "1_1") (pintype "passive"))
      (node (ref "R56") (pin "1") (pinfunction "1_1") (pintype "passive"))
      (node (ref "R62") (pin "1") (pinfunction "1_1") (pintype "passive"))
      (node (ref "R63") (pin "1") (pinfunction "1_1") (pintype "passive"))
      (node (ref "R8") (pin "1") (pinfunction "1_1") (pintype "passive"))
    )
    (net (code "27") (name "HALL_A_S") (class "Default")
      (node (ref "R42") (pin "1") (pinfunction "1_1") (pintype "passive"))
    )
    (net (code "28") (name "HALL_B_S") (class "Default")
      (node (ref "R45") (pin "1") (pinfunction "1_1") (pintype "passive"))
    )
    (net (code "29") (name "HALL_C_S") (class "Default")
      (node (ref "R46") (pin "1") (pinfunction "1_1") (pintype "passive"))
    )
    (net (code "30") (name "HV_BUF") (class "Default")
      (node (ref "R36") (pin "1") (pinfunction "1_1") (pintype "passive"))
    )
    (net (code "31") (name "IU_5VR") (class "Default")
      (node (ref "J1") (pin "3") (pinfunction "OUT_3") (pintype "passive"))
      (node (ref "R3") (pin "2") (pinfunction "2_2") (pintype "passive"))
    )
    (net (code "32") (name "IU_BUF") (class "Default")
      (node (ref "C13") (pin "1") (pinfunction "1_1") (pintype "passive"))
      (node (ref "IC1") (pin "2") (pinfunction "1IN-_2") (pintype "passive"))
      (node (ref "IC1") (pin "5") (pinfunction "2IN+_5") (pintype "passive"))
      (node (ref "IC3") (pin "1") (pinfunction "A_1") (pintype "passive"))
      (node (ref "R4") (pin "1") (pinfunction "1_1") (pintype "passive"))
    )
    (net (code "33") (name "IV_5VR") (class "Default")
      (node (ref "J2") (pin "3") (pinfunction "OUT_3") (pintype "passive"))
      (node (ref "R10") (pin "2") (pinfunction "2_2") (pintype "passive"))
    )
    (net (code "34") (name "IV_BUF") (class "Default")
      (node (ref "C25") (pin "1") (pinfunction "1_1") (pintype "passive"))
      (node (ref "IC4") (pin "2") (pinfunction "1IN-_2") (pintype "passive"))
      (node (ref "IC4") (pin "5") (pinfunction "2IN+_5") (pintype "passive"))
      (node (ref "IC8") (pin "1") (pinfunction "A_1") (pintype "passive"))
      (node (ref "R11") (pin "1") (pinfunction "1_1") (pintype "passive"))
    )
    (net (code "35") (name "IW_5VR") (class "Default")
      (node (ref "J3") (pin "3") (pinfunction "OUT_3") (pintype "passive"))
      (node (ref "R21") (pin "2") (pinfunction "2_2") (pintype "passive"))
    )
    (net (code "36") (name "IW_BUF") (class "Default")
      (node (ref "C34") (pin "1") (pinfunction "1_1") (pintype "passive"))
      (node (ref "IC11") (pin "1") (pinfunction "A_1") (pintype "passive"))
      (node (ref "IC6") (pin "2") (pinfunction "1IN-_2") (pintype "passive"))
      (node (ref "IC6") (pin "5") (pinfunction "2IN+_5") (pintype "passive"))
      (node (ref "R23") (pin "1") (pinfunction "1_1") (pintype "passive"))
    )
    (net (code "37") (name "MCU_RESET") (class "Default")
      (node (ref "JP5") (pin "5") (pinfunction "5_5") (pintype "passive"))
    )
    (net (code "38") (name "MOTOR_PWM_S") (class "Default")
      (node (ref "R47") (pin "1") (pinfunction "1_1") (pintype "passive"))
    )
    (net (code "39") (name "NTC_MOTOR_S") (class "Default")
      (node (ref "IC9") (pin "1") (pinfunction "OUT_1") (pintype "output"))
      (node (ref "IC9") (pin "4") (pinfunction "IN-_4") (pintype "passive"))
    )
    (net (code "40") (name "Net-(C15-Pad1)") (class "Default")
      (node (ref "C15") (pin "1") (pinfunction "1_1") (pintype "passive"))
      (node (ref "R7") (pin "2") (pinfunction "2_2") (pintype "passive"))
    )
    (net (code "41") (name "Net-(C26-Pad1)") (class "Default")
      (node (ref "C26") (pin "1") (pinfunction "1_1") (pintype "passive"))
      (node (ref "R13") (pin "2") (pinfunction "2_2") (pintype "passive"))
    )
    (net (code "42") (name "Net-(C35-Pad1)") (class "Default")
      (node (ref "C35") (pin "1") (pinfunction "1_1") (pintype "passive"))
      (node (ref "R27") (pin "2") (pinfunction "2_2") (pintype "passive"))
    )
    (net (code "43") (name "Net-(C43-Pad1)") (class "Default")
      (node (ref "C43") (pin "1") (pinfunction "1_1") (pintype "passive"))
      (node (ref "R37") (pin "1") (pinfunction "1_1") (pintype "passive"))
    )
    (net (code "44") (name "Net-(C44-Pad1)") (class "Default")
      (node (ref "C44") (pin "1") (pinfunction "1_1") (pintype "passive"))
      (node (ref "R30") (pin "1") (pinfunction "1_1") (pintype "passive"))
      (node (ref "R35") (pin "2") (pinfunction "2_2") (pintype "passive"))
      (node (ref "R39") (pin "2") (pinfunction "2_2") (pintype "passive"))
    )
    (net (code "45") (name "Net-(C45-Pad1)") (class "Default")
      (node (ref "C45") (pin "1") (pinfunction "1_1") (pintype "passive"))
      (node (ref "R35") (pin "1") (pinfunction "1_1") (pintype "passive"))
      (node (ref "R36") (pin "2") (pinfunction "2_2") (pintype "passive"))
    )
    (net (code "46") (name "Net-(C52-Pad1)") (class "Default")
      (node (ref "C52") (pin "1") (pinfunction "1_1") (pintype "passive"))
      (node (ref "R52") (pin "1") (pinfunction "1_1") (pintype "passive"))
    )
    (net (code "47") (name "Net-(C57-Pad1)") (class "Default")
      (node (ref "C57") (pin "1") (pinfunction "1_1") (pintype "passive"))
      (node (ref "R59") (pin "1") (pinfunction "1_1") (pintype "passive"))
    )
    (net (code "48") (name "Net-(DR4-K)") (class "Default")
      (node (ref "DR4") (pin "2") (pinfunction "K_2") (pintype "passive"))
      (node (ref "R17") (pin "1") (pinfunction "1_1") (pintype "passive"))
      (node (ref "R22") (pin "2") (pinfunction "2_2") (pintype "passive"))
      (node (ref "VD1") (pin "1") (pinfunction "A_1") (pintype "passive"))
    )
    (net (code "49") (name "Net-(DR5-K)") (class "Default")
      (node (ref "DR5") (pin "2") (pinfunction "K_2") (pintype "passive"))
      (node (ref "R18") (pin "1") (pinfunction "1_1") (pintype "passive"))
      (node (ref "R24") (pin "2") (pinfunction "2_2") (pintype "passive"))
      (node (ref "VD2") (pin "1") (pinfunction "A_1") (pintype "passive"))
    )
    (net (code "50") (name "Net-(DR6-K)") (class "Default")
      (node (ref "DR6") (pin "2") (pinfunction "K_2") (pintype "passive"))
      (node (ref "R19") (pin "1") (pinfunction "1_1") (pintype "passive"))
      (node (ref "R26") (pin "2") (pinfunction "2_2") (pintype "passive"))
      (node (ref "VD3") (pin "1") (pinfunction "A_1") (pintype "passive"))
    )
    (net (code "51") (name "Net-(F1-Pad2)") (class "Default")
      (node (ref "F1") (pin "2") (pinfunction "2_2") (pintype "passive"))
      (node (ref "R1") (pin "2") (pinfunction "2_2") (pintype "passive"))
    )
    (net (code "52") (name "Net-(F2-Pad2)") (class "Default")
      (node (ref "F2") (pin "2") (pinfunction "2_2") (pintype "passive"))
      (node (ref "F4") (pin "1") (pinfunction "1_1") (pintype "passive"))
    )
    (net (code "53") (name "Net-(IC2-IN+)") (class "Default")
      (node (ref "IC2") (pin "3") (pinfunction "IN+_3") (pintype "input"))
      (node (ref "R3") (pin "1") (pinfunction "1_1") (pintype "passive"))
      (node (ref "R5") (pin "2") (pinfunction "2_2") (pintype "passive"))
    )
    (net (code "54") (name "Net-(IC2-IN-)") (class "Default")
      (node (ref "IC2") (pin "1") (pinfunction "OUT_1") (pintype "output"))
      (node (ref "IC2") (pin "4") (pinfunction "IN-_4") (pintype "input"))
      (node (ref "R4") (pin "2") (pinfunction "2_2") (pintype "passive"))
    )
    (net (code "55") (name "Net-(IC3-B)") (class "Default")
      (node (ref "IC3") (pin "2") (pinfunction "B_2") (pintype "passive"))
      (node (ref "R7") (pin "1") (pinfunction "1_1") (pintype "passive"))
    )
    (net (code "56") (name "Net-(IC5-CANH)") (class "Default")
      (node (ref "B1") (pin "1") (pinfunction "1_1") (pintype "passive"))
      (node (ref "C18") (pin "1") (pinfunction "1_1") (pintype "passive"))
      (node (ref "IC5") (pin "7") (pinfunction "CANH_7") (pintype "passive"))
      (node (ref "L1") (pin "4") (pinfunction "4_4") (pintype "passive"))
      (node (ref "R9") (pin "1") (pinfunction "1_1") (pintype "passive"))
    )
    (net (code "57") (name "Net-(IC5-CANL)") (class "Default")
      (node (ref "B1") (pin "2") (pinfunction "2_2") (pintype "passive"))
      (node (ref "C22") (pin "2") (pinfunction "2_2") (pintype "passive"))
      (node (ref "IC5") (pin "6") (pinfunction "CANL_6") (pintype "passive"))
      (node (ref "L1") (pin "1") (pinfunction "1_1") (pintype "passive"))
      (node (ref "R9") (pin "2") (pinfunction "2_2") (pintype "passive"))
    )
    (net (code "58") (name "Net-(IC5-Rs)") (class "Default")
      (node (ref "IC5") (pin "8") (pinfunction "Rs_8") (pintype "passive"))
      (node (ref "R8") (pin "2") (pinfunction "2_2") (pintype "passive"))
    )
    (net (code "59") (name "Net-(IC7-IN+)") (class "Default")
      (node (ref "IC7") (pin "3") (pinfunction "IN+_3") (pintype "input"))
      (node (ref "R10") (pin "1") (pinfunction "1_1") (pintype "passive"))
      (node (ref "R12") (pin "2") (pinfunction "2_2") (pintype "passive"))
    )
    (net (code "60") (name "Net-(IC7-IN-)") (class "Default")
      (node (ref "IC7") (pin "1") (pinfunction "OUT_1") (pintype "output"))
      (node (ref "IC7") (pin "4") (pinfunction "IN-_4") (pintype "input"))
      (node (ref "R11") (pin "2") (pinfunction "2_2") (pintype "passive"))
    )
    (net (code "61") (name "Net-(IC8-B)") (class "Default")
      (node (ref "IC8") (pin "2") (pinfunction "B_2") (pintype "passive"))
      (node (ref "R13") (pin "1") (pinfunction "1_1") (pintype "passive"))
    )
    (net (code "62") (name "Net-(IC9-IN+)") (class "Default")
      (node (ref "C33") (pin "2") (pinfunction "2_2") (pintype "passive"))
      (node (ref "IC9") (pin "3") (pinfunction "IN+_3") (pintype "passive"))
      (node (ref "R20") (pin "2") (pinfunction "2_2") (pintype "passive"))
    )
    (net (code "63") (name "Net-(IC10-IN+)") (class "Default")
      (node (ref "IC10") (pin "3") (pinfunction "IN+_3") (pintype "input"))
      (node (ref "R21") (pin "1") (pinfunction "1_1") (pintype "passive"))
      (node (ref "R25") (pin "2") (pinfunction "2_2") (pintype "passive"))
    )
    (net (code "64") (name "Net-(IC10-IN-)") (class "Default")
      (node (ref "IC10") (pin "1") (pinfunction "OUT_1") (pintype "output"))
      (node (ref "IC10") (pin "4") (pinfunction "IN-_4") (pintype "input"))
      (node (ref "R23") (pin "2") (pinfunction "2_2") (pintype "passive"))
    )
    (net (code "65") (name "Net-(IC11-B)") (class "Default")
      (node (ref "IC11") (pin "2") (pinfunction "B_2") (pintype "passive"))
      (node (ref "R27") (pin "1") (pinfunction "1_1") (pintype "passive"))
    )
    (net (code "66") (name "Net-(IC12-A1)") (class "Default")
      (node (ref "C49") (pin "2") (pinfunction "2_2") (pintype "passive"))
      (node (ref "IC12") (pin "2") (pinfunction "A1_2") (pintype "passive"))
      (node (ref "R38") (pin "1") (pinfunction "1_1") (pintype "passive"))
    )
    (net (code "67") (name "Net-(IC12-A2)") (class "Default")
      (node (ref "C48") (pin "2") (pinfunction "2_2") (pintype "passive"))
      (node (ref "IC12") (pin "3") (pinfunction "A2_3") (pintype "passive"))
      (node (ref "R41") (pin "1") (pinfunction "1_1") (pintype "passive"))
    )
    (net (code "68") (name "Net-(IC12-A3)") (class "Default")
      (node (ref "C47") (pin "2") (pinfunction "2_2") (pintype "passive"))
      (node (ref "IC12") (pin "4") (pinfunction "A3_4") (pintype "passive"))
      (node (ref "R44") (pin "1") (pinfunction "1_1") (pintype "passive"))
    )
    (net (code "69") (name "Net-(IC12-A4)") (class "Default")
      (node (ref "C53") (pin "2") (pinfunction "2_2") (pintype "passive"))
      (node (ref "IC12") (pin "5") (pinfunction "A4_5") (pintype "passive"))
      (node (ref "R53") (pin "1") (pinfunction "1_1") (pintype "passive"))
    )
    (net (code "70") (name "Net-(IC12-B1)") (class "Default")
      (node (ref "IC12") (pin "18") (pinfunction "B1_18") (pintype "passive"))
      (node (ref "R42") (pin "2") (pinfunction "2_2") (pintype "passive"))
    )
    (net (code "71") (name "Net-(IC12-B2)") (class "Default")
      (node (ref "IC12") (pin "17") (pinfunction "B2_17") (pintype "passive"))
      (node (ref "R45") (pin "2") (pinfunction "2_2") (pintype "passive"))
    )
    (net (code "72") (name "Net-(IC12-B3)") (class "Default")
      (node (ref "IC12") (pin "16") (pinfunction "B3_16") (pintype "passive"))
      (node (ref "R46") (pin "2") (pinfunction "2_2") (pintype "passive"))
    )
    (net (code "73") (name "Net-(IC12-B4)") (class "Default")
      (node (ref "IC12") (pin "15") (pinfunction "B4_15") (pintype "passive"))
      (node (ref "R47") (pin "2") (pinfunction "2_2") (pintype "passive"))
    )
    (net (code "74") (name "Net-(IC13-A)") (class "Default")
      (node (ref "IC13") (pin "1") (pinfunction "A_1") (pintype "passive"))
      (node (ref "R37") (pin "2") (pinfunction "2_2") (pintype "passive"))
    )
    (net (code "75") (name "Net-(IC14-IN+)") (class "Default")
      (node (ref "C43") (pin "2") (pinfunction "2_2") (pintype "passive"))
      (node (ref "IC14") (pin "3") (pinfunction "IN+_3") (pintype "input"))
      (node (ref "R34") (pin "1") (pinfunction "1_1") (pintype "passive"))
      (node (ref "R43") (pin "2") (pinfunction "2_2") (pintype "passive"))
    )
    (net (code "76") (name "Net-(IC14-IN-)") (class "Default")
      (node (ref "IC14") (pin "1") (pinfunction "OUT_1") (pintype "output"))
      (node (ref "IC14") (pin "4") (pinfunction "IN-_4") (pintype "input"))
      (node (ref "R40") (pin "2") (pinfunction "2_2") (pintype "passive"))
    )
    (net (code "77") (name "Net-(IC15-IN+)") (class "Default")
      (node (ref "IC15") (pin "3") (pinfunction "IN+_3") (pintype "passive"))
      (node (ref "R48") (pin "1") (pinfunction "1_1") (pintype "passive"))
      (node (ref "R51") (pin "2") (pinfunction "2_2") (pintype "passive"))
    )
    (net (code "78") (name "Net-(IC15-IN-)") (class "Default")
      (node (ref "IC15") (pin "1") (pinfunction "OUT_1") (pintype "output"))
      (node (ref "IC15") (pin "4") (pinfunction "IN-_4") (pintype "passive"))
      (node (ref "R50") (pin "2") (pinfunction "2_2") (pintype "passive"))
    )
    (net (code "79") (name "Net-(IC16-A)") (class "Default")
      (node (ref "IC16") (pin "1") (pinfunction "A_1") (pintype "passive"))
      (node (ref "R52") (pin "2") (pinfunction "2_2") (pintype "passive"))
    )
    (net (code "80") (name "Net-(IC17-IN+)") (class "Default")
      (node (ref "C52") (pin "2") (pinfunction "2_2") (pintype "passive"))
      (node (ref "IC17") (pin "3") (pinfunction "IN+_3") (pintype "input"))
      (node (ref "R49") (pin "1") (pinfunction "1_1") (pintype "passive"))
      (node (ref "R55") (pin "2") (pinfunction "2_2") (pintype "passive"))
    )
    (net (code "81") (name "Net-(IC17-IN-)") (class "Default")
      (node (ref "IC17") (pin "1") (pinfunction "OUT_1") (pintype "output"))
      (node (ref "IC17") (pin "4") (pinfunction "IN-_4") (pintype "input"))
      (node (ref "R54") (pin "2") (pinfunction "2_2") (pintype "passive"))
    )
    (net (code "82") (name "Net-(IC18-A)") (class "Default")
      (node (ref "IC18") (pin "1") (pinfunction "A_1") (pintype "passive"))
      (node (ref "R59") (pin "2") (pinfunction "2_2") (pintype "passive"))
    )
    (net (code "83") (name "Net-(IC19-IN+)") (class "Default")
      (node (ref "C57") (pin "2") (pinfunction "2_2") (pintype "passive"))
      (node (ref "IC19") (pin "3") (pinfunction "IN+_3") (pintype "input"))
      (node (ref "R57") (pin "1") (pinfunction "1_1") (pintype "passive"))
      (node (ref "R62") (pin "2") (pinfunction "2_2") (pintype "passive"))
    )
    (net (code "84") (name "Net-(IC19-IN-)") (class "Default")
      (node (ref "IC19") (pin "1") (pinfunction "OUT_1") (pintype "output"))
      (node (ref "IC19") (pin "4") (pinfunction "IN-_4") (pintype "input"))
      (node (ref "R60") (pin "2") (pinfunction "2_2") (pintype "passive"))
    )
    (net (code "85") (name "Net-(IC20-IN+)") (class "Default")
      (node (ref "IC20") (pin "3") (pinfunction "IN+_3") (pintype "passive"))
      (node (ref "R58") (pin "1") (pinfunction "1_1") (pintype "passive"))
      (node (ref "R63") (pin "2") (pinfunction "2_2") (pintype "passive"))
    )
    (net (code "86") (name "Net-(IC20-IN-)") (class "Default")
      (node (ref "IC20") (pin "1") (pinfunction "OUT_1") (pintype "output"))
      (node (ref "IC20") (pin "4") (pinfunction "IN-_4") (pintype "passive"))
      (node (ref "R61") (pin "2") (pinfunction "2_2") (pintype "passive"))
    )
    (net (code "87") (name "Net-(JP6-Pad3)") (class "Default")
      (node (ref "JP6") (pin "3") (pinfunction "3_3") (pintype "passive"))
      (node (ref "R2") (pin "2") (pinfunction "2_2") (pintype "passive"))
    )
    (net (code "88") (name "PHASE_U") (class "Default")
      (node (ref "JP9") (pin "1") (pinfunction "1_1") (pintype "passive"))
      (node (ref "JP9") (pin "2") (pinfunction "2_2") (pintype "passive"))
      (node (ref "JP9") (pin "3") (pinfunction "3_3") (pintype "passive"))
      (node (ref "JP9") (pin "4") (pinfunction "4_4") (pintype "passive"))
      (node (ref "R34") (pin "2") (pinfunction "2_2") (pintype "passive"))
    )
    (net (code "89") (name "PHASE_V") (class "Default")
      (node (ref "JP8") (pin "1") (pinfunction "1_1") (pintype "passive"))
      (node (ref "JP8") (pin "2") (pinfunction "2_2") (pintype "passive"))
      (node (ref "JP8") (pin "3") (pinfunction "3_3") (pintype "passive"))
      (node (ref "JP8") (pin "4") (pinfunction "4_4") (pintype "passive"))
      (node (ref "R49") (pin "2") (pinfunction "2_2") (pintype "passive"))
    )
    (net (code "90") (name "PHASE_W") (class "Default")
      (node (ref "JP10") (pin "1") (pinfunction "1_1") (pintype "passive"))
      (node (ref "JP10") (pin "2") (pinfunction "2_2") (pintype "passive"))
      (node (ref "JP10") (pin "3") (pinfunction "3_3") (pintype "passive"))
      (node (ref "JP10") (pin "4") (pinfunction "4_4") (pintype "passive"))
      (node (ref "R57") (pin "2") (pinfunction "2_2") (pintype "passive"))
    )
    (net (code "91") (name "PHA_FILTER_SEL") (class "Default")
      (node (ref "IC13") (pin "4") (pinfunction "Y_4") (pintype "passive"))
      (node (ref "IC16") (pin "4") (pinfunction "Y_4") (pintype "passive"))
      (node (ref "IC18") (pin "4") (pinfunction "Y_4") (pintype "passive"))
    )
    (net (code "92") (name "SERVO_S") (class "Default")
      (node (ref "C37") (pin "2") (pinfunction "2_2") (pintype "passive"))
      (node (ref "R26") (pin "1") (pinfunction "1_1") (pintype "passive"))
    )
    (net (code "93") (name "SPI_MISO") (class "Default")
      (node (ref "JP4") (pin "4") (pinfunction "4_4") (pintype "passive"))
    )
    (net (code "94") (name "SPI_MOSI") (class "Default")
      (node (ref "JP4") (pin "5") (pinfunction "5_5") (pintype "passive"))
    )
    (net (code "95") (name "SPI_NSS") (class "Default")
      (node (ref "JP4") (pin "2") (pinfunction "2_2") (pintype "passive"))
    )
    (net (code "96") (name "SPI_SCK") (class "Default")
      (node (ref "JP4") (pin "3") (pinfunction "3_3") (pintype "passive"))
    )
    (net (code "97") (name "SWCLK") (class "Default")
      (node (ref "JP5") (pin "2") (pinfunction "2_2") (pintype "passive"))
    )
    (net (code "98") (name "SWDIO") (class "Default")
      (node (ref "JP5") (pin "3") (pinfunction "3_3") (pintype "passive"))
    )
    (net (code "99") (name "VCC120") (class "Default")
      (node (ref "R2") (pin "1") (pinfunction "1_1") (pintype "passive"))
      (node (ref "R30") (pin "2") (pinfunction "2_2") (pintype "passive"))
    )
    (net (code "100") (name "VCCANA5") (class "Default")
      (node (ref "C10") (pin "1") (pinfunction "1_1") (pintype "passive"))
      (node (ref "C11") (pin "2") (pinfunction "2_2") (pintype "passive"))
      (node (ref "C12") (pin "1") (pinfunction "1_1") (pintype "passive"))
      (node (ref "C14") (pin "1") (pinfunction "1_1") (pintype "passive"))
      (node (ref "C16") (pin "1") (pinfunction "1_1") (pintype "passive"))
      (node (ref "C20") (pin "1") (pinfunction "1_1") (pintype "passive"))
      (node (ref "C21") (pin "1") (pinfunction "1_1") (pintype "passive"))
      (node (ref "C23") (pin "2") (pinfunction "2_2") (pintype "passive"))
      (node (ref "C24") (pin "1") (pinfunction "1_1") (pintype "passive"))
      (node (ref "C27") (pin "1") (pinfunction "1_1") (pintype "passive"))
      (node (ref "C28") (pin "1") (pinfunction "1_1") (pintype "passive"))
      (node (ref "C29") (pin "2") (pinfunction "2_2") (pintype "passive"))
      (node (ref "C3") (pin "1") (pinfunction "1_1") (pintype "passive"))
      (node (ref "C30") (pin "1") (pinfunction "1_1") (pintype "passive"))
      (node (ref "C36") (pin "1") (pinfunction "1_1") (pintype "passive"))
      (node (ref "C4") (pin "1") (pinfunction "1_1") (pintype "passive"))
      (node (ref "C41") (pin "1") (pinfunction "1_1") (pintype "passive"))
      (node (ref "C46") (pin "1") (pinfunction "1_1") (pintype "passive"))
      (node (ref "C50") (pin "1") (pinfunction "1_1") (pintype "passive"))
      (node (ref "C54") (pin "1") (pinfunction "1_1") (pintype "passive"))
      (node (ref "C55") (pin "1") (pinfunction "1_1") (pintype "passive"))
      (node (ref "C58") (pin "1") (pinfunction "1_1") (pintype "passive"))
      (node (ref "C9") (pin "1") (pinfunction "1_1") (pintype "passive"))
      (node (ref "F1") (pin "1") (pinfunction "1_1") (pintype "passive"))
      (node (ref "IC1") (pin "8") (pinfunction "VCC_8") (pintype "passive"))
      (node (ref "IC10") (pin "5") (pinfunction "V+_5") (pintype "power_in"))
      (node (ref "IC11") (pin "5") (pinfunction "VCC_5") (pintype "passive"))
      (node (ref "IC13") (pin "5") (pinfunction "VCC_5") (pintype "passive"))
      (node (ref "IC14") (pin "5") (pinfunction "V+_5") (pintype "power_in"))
      (node (ref "IC15") (pin "5") (pinfunction "V+_5") (pintype "passive"))
      (node (ref "IC16") (pin "5") (pinfunction "VCC_5") (pintype "passive"))
      (node (ref "IC17") (pin "5") (pinfunction "V+_5") (pintype "power_in"))
      (node (ref "IC18") (pin "5") (pinfunction "VCC_5") (pintype "passive"))
      (node (ref "IC19") (pin "5") (pinfunction "V+_5") (pintype "power_in"))
      (node (ref "IC2") (pin "5") (pinfunction "V+_5") (pintype "power_in"))
      (node (ref "IC20") (pin "5") (pinfunction "V+_5") (pintype "passive"))
      (node (ref "IC3") (pin "5") (pinfunction "VCC_5") (pintype "passive"))
      (node (ref "IC4") (pin "8") (pinfunction "VCC_8") (pintype "passive"))
      (node (ref "IC6") (pin "8") (pinfunction "VCC_8") (pintype "passive"))
      (node (ref "IC7") (pin "5") (pinfunction "V+_5") (pintype "power_in"))
      (node (ref "IC8") (pin "5") (pinfunction "VCC_5") (pintype "passive"))
      (node (ref "J1") (pin "1") (pinfunction "VDD_1") (pintype "passive"))
      (node (ref "J2") (pin "1") (pinfunction "VDD_1") (pintype "passive"))
      (node (ref "J3") (pin "1") (pinfunction "VDD_1") (pintype "passive"))
      (node (ref "R14") (pin "2") (pinfunction "2_2") (pintype "passive"))
      (node (ref "R28") (pin "2") (pinfunction "2_2") (pintype "passive"))
    )
    (net (code "101") (name "VCCDIG5") (class "Default")
      (node (ref "C42") (pin "1") (pinfunction "1_1") (pintype "passive"))
      (node (ref "C7") (pin "1") (pinfunction "1_1") (pintype "passive"))
      (node (ref "C8") (pin "1") (pinfunction "1_1") (pintype "passive"))
      (node (ref "F2") (pin "1") (pinfunction "1_1") (pintype "passive"))
      (node (ref "IC12") (pin "1") (pinfunction "DIR_1") (pintype "passive"))
      (node (ref "IC12") (pin "20") (pinfunction "VCC_20") (pintype "passive"))
      (node (ref "JP2") (pin "2") (pinfunction "2_2") (pintype "passive"))
      (node (ref "R31") (pin "2") (pinfunction "2_2") (pintype "passive"))
      (node (ref "R32") (pin "2") (pinfunction "2_2") (pintype "passive"))
      (node (ref "R33") (pin "2") (pinfunction "2_2") (pintype "passive"))
    )
    (net (code "102") (name "VCCMCU3V3") (class "Default")
      (node (ref "C19") (pin "1") (pinfunction "1_1") (pintype "passive"))
      (node (ref "IC5") (pin "3") (pinfunction "VCC_3") (pintype "passive"))
      (node (ref "IC9") (pin "5") (pinfunction "V+_5") (pintype "passive"))
      (node (ref "JP4") (pin "6") (pinfunction "6_6") (pintype "passive"))
      (node (ref "JP5") (pin "4") (pinfunction "4_4") (pintype "passive"))
      (node (ref "R15") (pin "2") (pinfunction "2_2") (pintype "passive"))
      (node (ref "R17") (pin "2") (pinfunction "2_2") (pintype "passive"))
      (node (ref "R18") (pin "2") (pinfunction "2_2") (pintype "passive"))
      (node (ref "R19") (pin "2") (pinfunction "2_2") (pintype "passive"))
      (node (ref "R6") (pin "2") (pinfunction "2_2") (pintype "passive"))
    )
    (net (code "103") (name "VU_BUF") (class "Default")
      (node (ref "R40") (pin "1") (pinfunction "1_1") (pintype "passive"))
    )
    (net (code "104") (name "VV_BUF") (class "Default")
      (node (ref "R54") (pin "1") (pinfunction "1_1") (pintype "passive"))
    )
    (net (code "105") (name "VW_BUF") (class "Default")
      (node (ref "R60") (pin "1") (pinfunction "1_1") (pintype "passive"))
    )
    (net (code "106") (name "unconnected-(IC5-Vref-Pad5)") (class "Default")
      (node (ref "IC5") (pin "5") (pinfunction "Vref_5") (pintype "passive"))
    )
    (net (code "107") (name "unconnected-(IC12-B5-Pad14)") (class "Default")
      (node (ref "IC12") (pin "14") (pinfunction "B5_14") (pintype "passive"))
    )
    (net (code "108") (name "unconnected-(IC12-B6-Pad13)") (class "Default")
      (node (ref "IC12") (pin "13") (pinfunction "B6_13") (pintype "passive"))
    )
    (net (code "109") (name "unconnected-(IC12-B7-Pad12)") (class "Default")
      (node (ref "IC12") (pin "12") (pinfunction "B7_12") (pintype "passive"))
    )
    (net (code "110") (name "unconnected-(IC12-B8-Pad11)") (class "Default")
      (node (ref "IC12") (pin "11") (pinfunction "B8_11") (pintype "passive"))
    )
    (net (code "111") (name "unconnected-(JP6-Pad1)") (class "Default")
      (node (ref "JP6") (pin "1") (pinfunction "1_1") (pintype "passive"))
    )
    (net (code "112") (name "unconnected-(JP6-Pad2)") (class "Default")
      (node (ref "JP6") (pin "2") (pinfunction "2_2") (pintype "passive"))
    )
  )
)
